# central.net
KiCad netlist of a schematic drawn in EAGLE
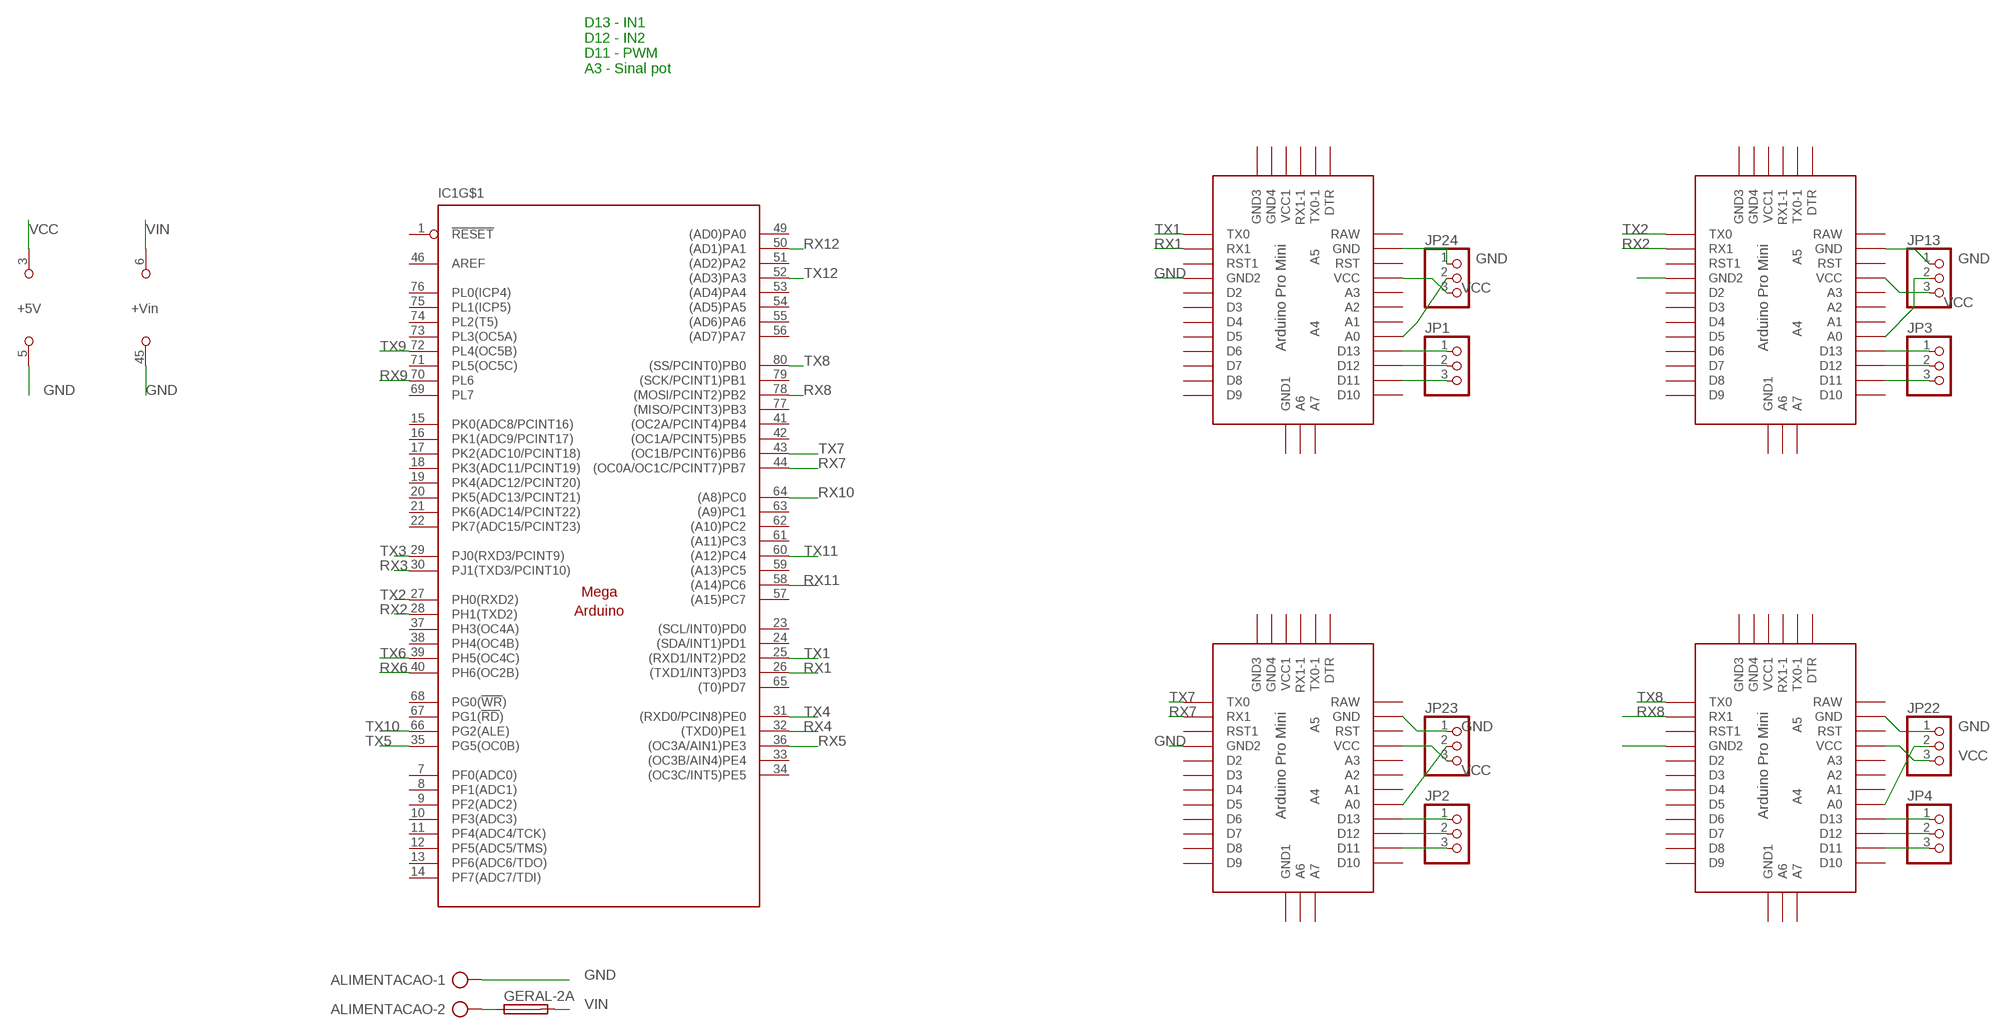
[diagram p0: schematic, sheet 1, part 1 of 2]
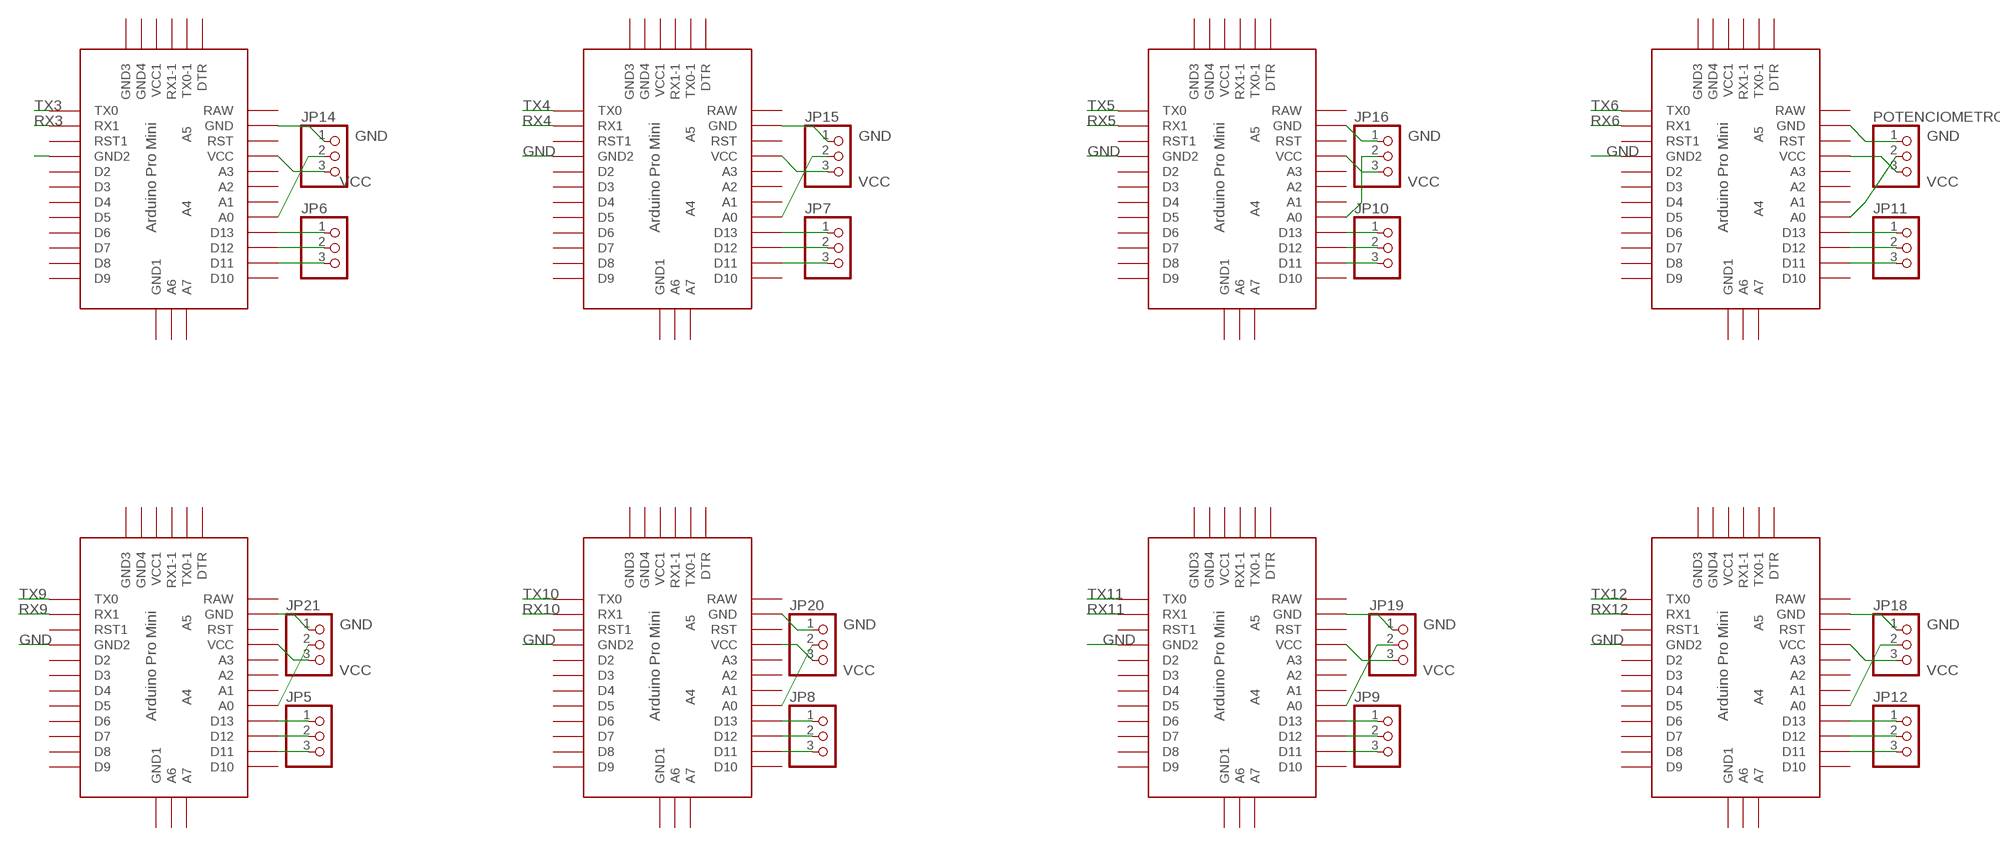
[diagram p1: schematic, sheet 1, part 2 of 2]

(export (version "E")
  (design (tool "Eeschema 10.0.6"))
  (components
    (comp (ref "ALIMENTACAO")
      (value "AK500/2")
      (footprint "eagle-import:AK500_2")
      (libsource (lib "eagle-import") (part "AK500/2"))
    )
    (comp (ref "GERAL-2A")
      (value "SH22,5A")
      (footprint "eagle-import:SH22,5A")
      (fields (field (name "MPN") "0031.7701.11"))
      (libsource (lib "eagle-import") (part "SH22,5A"))
    )
    (comp (ref "IC1")
      (value "MEGAARDUINO_22")
      (footprint "eagle-import:MEGA_ARDUINO_2")
      (libsource (lib "eagle-import") (part "MEGAARDUINO_22"))
    )
    (comp (ref "JP1")
      (value "PINHD-1X3")
      (footprint "eagle-import:1X03")
      (libsource (lib "eagle-import") (part "PINHD-1X3"))
    )
    (comp (ref "JP2")
      (value "PINHD-1X3")
      (footprint "eagle-import:1X03")
      (libsource (lib "eagle-import") (part "PINHD-1X3"))
    )
    (comp (ref "JP3")
      (value "PINHD-1X3")
      (footprint "eagle-import:1X03")
      (libsource (lib "eagle-import") (part "PINHD-1X3"))
    )
    (comp (ref "JP4")
      (value "PINHD-1X3")
      (footprint "eagle-import:1X03")
      (libsource (lib "eagle-import") (part "PINHD-1X3"))
    )
    (comp (ref "JP5")
      (value "PINHD-1X3")
      (footprint "eagle-import:1X03")
      (libsource (lib "eagle-import") (part "PINHD-1X3"))
    )
    (comp (ref "JP6")
      (value "PINHD-1X3")
      (footprint "eagle-import:1X03")
      (libsource (lib "eagle-import") (part "PINHD-1X3"))
    )
    (comp (ref "JP7")
      (value "PINHD-1X3")
      (footprint "eagle-import:1X03")
      (libsource (lib "eagle-import") (part "PINHD-1X3"))
    )
    (comp (ref "JP8")
      (value "PINHD-1X3")
      (footprint "eagle-import:1X03")
      (libsource (lib "eagle-import") (part "PINHD-1X3"))
    )
    (comp (ref "JP9")
      (value "PINHD-1X3")
      (footprint "eagle-import:1X03")
      (libsource (lib "eagle-import") (part "PINHD-1X3"))
    )
    (comp (ref "JP10")
      (value "PINHD-1X3")
      (footprint "eagle-import:1X03")
      (libsource (lib "eagle-import") (part "PINHD-1X3"))
    )
    (comp (ref "JP11")
      (value "PINHD-1X3")
      (footprint "eagle-import:1X03")
      (libsource (lib "eagle-import") (part "PINHD-1X3"))
    )
    (comp (ref "JP12")
      (value "PINHD-1X3")
      (footprint "eagle-import:1X03")
      (libsource (lib "eagle-import") (part "PINHD-1X3"))
    )
    (comp (ref "JP13")
      (value "PINHD-1X3")
      (footprint "eagle-import:1X03")
      (libsource (lib "eagle-import") (part "PINHD-1X3"))
    )
    (comp (ref "JP14")
      (value "PINHD-1X3")
      (footprint "eagle-import:1X03")
      (libsource (lib "eagle-import") (part "PINHD-1X3"))
    )
    (comp (ref "JP15")
      (value "PINHD-1X3")
      (footprint "eagle-import:1X03")
      (libsource (lib "eagle-import") (part "PINHD-1X3"))
    )
    (comp (ref "JP16")
      (value "PINHD-1X3")
      (footprint "eagle-import:1X03")
      (libsource (lib "eagle-import") (part "PINHD-1X3"))
    )
    (comp (ref "JP18")
      (value "PINHD-1X3")
      (footprint "eagle-import:1X03")
      (libsource (lib "eagle-import") (part "PINHD-1X3"))
    )
    (comp (ref "JP19")
      (value "PINHD-1X3")
      (footprint "eagle-import:1X03")
      (libsource (lib "eagle-import") (part "PINHD-1X3"))
    )
    (comp (ref "JP20")
      (value "PINHD-1X3")
      (footprint "eagle-import:1X03")
      (libsource (lib "eagle-import") (part "PINHD-1X3"))
    )
    (comp (ref "JP21")
      (value "PINHD-1X3")
      (footprint "eagle-import:1X03")
      (libsource (lib "eagle-import") (part "PINHD-1X3"))
    )
    (comp (ref "JP22")
      (value "PINHD-1X3")
      (footprint "eagle-import:1X03")
      (libsource (lib "eagle-import") (part "PINHD-1X3"))
    )
    (comp (ref "JP23")
      (value "PINHD-1X3")
      (footprint "eagle-import:1X03")
      (libsource (lib "eagle-import") (part "PINHD-1X3"))
    )
    (comp (ref "JP24")
      (value "PINHD-1X3")
      (footprint "eagle-import:1X03")
      (libsource (lib "eagle-import") (part "PINHD-1X3"))
    )
    (comp (ref "POTENCIOMETRO")
      (value "PINHD-1X3")
      (footprint "eagle-import:1X03")
      (libsource (lib "eagle-import") (part "PINHD-1X3"))
    )
    (comp (ref "U$1")
      (value "ABK-PRO-MINI")
      (footprint "eagle-import:ABK-PRO-MINI")
      (libsource (lib "eagle-import") (part "ABK-PRO-MINI"))
    )
    (comp (ref "U$2")
      (value "ABK-PRO-MINI")
      (footprint "eagle-import:ABK-PRO-MINI")
      (libsource (lib "eagle-import") (part "ABK-PRO-MINI"))
    )
    (comp (ref "U$3")
      (value "ABK-PRO-MINI")
      (footprint "eagle-import:ABK-PRO-MINI")
      (libsource (lib "eagle-import") (part "ABK-PRO-MINI"))
    )
    (comp (ref "U$4")
      (value "ABK-PRO-MINI")
      (footprint "eagle-import:ABK-PRO-MINI")
      (libsource (lib "eagle-import") (part "ABK-PRO-MINI"))
    )
    (comp (ref "U$5")
      (value "ABK-PRO-MINI")
      (footprint "eagle-import:ABK-PRO-MINI")
      (libsource (lib "eagle-import") (part "ABK-PRO-MINI"))
    )
    (comp (ref "U$6")
      (value "ABK-PRO-MINI")
      (footprint "eagle-import:ABK-PRO-MINI")
      (libsource (lib "eagle-import") (part "ABK-PRO-MINI"))
    )
    (comp (ref "U$7")
      (value "ABK-PRO-MINI")
      (footprint "eagle-import:ABK-PRO-MINI")
      (libsource (lib "eagle-import") (part "ABK-PRO-MINI"))
    )
    (comp (ref "U$8")
      (value "ABK-PRO-MINI")
      (footprint "eagle-import:ABK-PRO-MINI")
      (libsource (lib "eagle-import") (part "ABK-PRO-MINI"))
    )
    (comp (ref "U$9")
      (value "ABK-PRO-MINI")
      (footprint "eagle-import:ABK-PRO-MINI")
      (libsource (lib "eagle-import") (part "ABK-PRO-MINI"))
    )
    (comp (ref "U$10")
      (value "ABK-PRO-MINI")
      (footprint "eagle-import:ABK-PRO-MINI")
      (libsource (lib "eagle-import") (part "ABK-PRO-MINI"))
    )
    (comp (ref "U$11")
      (value "ABK-PRO-MINI")
      (footprint "eagle-import:ABK-PRO-MINI")
      (libsource (lib "eagle-import") (part "ABK-PRO-MINI"))
    )
    (comp (ref "U$12")
      (value "ABK-PRO-MINI")
      (footprint "eagle-import:ABK-PRO-MINI")
      (libsource (lib "eagle-import") (part "ABK-PRO-MINI"))
    )
  )
  (nets
    (net (code "1") (name "/GND") (class "Default")
      (node (ref "ALIMENTACAO") (pin "1") (pinfunction "KL_1") (pintype "passive"))
      (node (ref "IC1") (pin "45") (pinfunction "GND_45") (pintype "power_in"))
      (node (ref "IC1") (pin "5") (pinfunction "GND_5") (pintype "power_in"))
      (node (ref "JP13") (pin "1") (pinfunction "1_1") (pintype "passive"))
      (node (ref "JP14") (pin "1") (pinfunction "1_1") (pintype "passive"))
      (node (ref "JP15") (pin "1") (pinfunction "1_1") (pintype "passive"))
      (node (ref "JP16") (pin "1") (pinfunction "1_1") (pintype "passive"))
      (node (ref "JP18") (pin "1") (pinfunction "1_1") (pintype "passive"))
      (node (ref "JP19") (pin "1") (pinfunction "1_1") (pintype "passive"))
      (node (ref "JP20") (pin "1") (pinfunction "1_1") (pintype "passive"))
      (node (ref "JP21") (pin "1") (pinfunction "1_1") (pintype "passive"))
      (node (ref "JP22") (pin "1") (pinfunction "1_1") (pintype "passive"))
      (node (ref "JP23") (pin "1") (pinfunction "1_1") (pintype "passive"))
      (node (ref "JP24") (pin "1") (pinfunction "1_1") (pintype "passive"))
      (node (ref "POTENCIOMETRO") (pin "1") (pinfunction "1_1") (pintype "passive"))
      (node (ref "U$1") (pin "GND") (pinfunction "GND_GND") (pintype "bidirectional"))
      (node (ref "U$1") (pin "GND1") (pinfunction "GND2_GND1") (pintype "bidirectional"))
      (node (ref "U$10") (pin "GND") (pinfunction "GND_GND") (pintype "bidirectional"))
      (node (ref "U$10") (pin "GND1") (pinfunction "GND2_GND1") (pintype "bidirectional"))
      (node (ref "U$11") (pin "GND") (pinfunction "GND_GND") (pintype "bidirectional"))
      (node (ref "U$11") (pin "GND1") (pinfunction "GND2_GND1") (pintype "bidirectional"))
      (node (ref "U$12") (pin "GND") (pinfunction "GND_GND") (pintype "bidirectional"))
      (node (ref "U$12") (pin "GND1") (pinfunction "GND2_GND1") (pintype "bidirectional"))
      (node (ref "U$2") (pin "GND") (pinfunction "GND_GND") (pintype "bidirectional"))
      (node (ref "U$2") (pin "GND1") (pinfunction "GND2_GND1") (pintype "bidirectional"))
      (node (ref "U$3") (pin "GND") (pinfunction "GND_GND") (pintype "bidirectional"))
      (node (ref "U$3") (pin "GND1") (pinfunction "GND2_GND1") (pintype "bidirectional"))
      (node (ref "U$4") (pin "GND") (pinfunction "GND_GND") (pintype "bidirectional"))
      (node (ref "U$4") (pin "GND1") (pinfunction "GND2_GND1") (pintype "bidirectional"))
      (node (ref "U$5") (pin "GND") (pinfunction "GND_GND") (pintype "bidirectional"))
      (node (ref "U$5") (pin "GND1") (pinfunction "GND2_GND1") (pintype "bidirectional"))
      (node (ref "U$6") (pin "GND") (pinfunction "GND_GND") (pintype "bidirectional"))
      (node (ref "U$6") (pin "GND1") (pinfunction "GND2_GND1") (pintype "bidirectional"))
      (node (ref "U$7") (pin "GND") (pinfunction "GND_GND") (pintype "bidirectional"))
      (node (ref "U$7") (pin "GND1") (pinfunction "GND2_GND1") (pintype "bidirectional"))
      (node (ref "U$8") (pin "GND") (pinfunction "GND_GND") (pintype "bidirectional"))
      (node (ref "U$8") (pin "GND1") (pinfunction "GND2_GND1") (pintype "bidirectional"))
      (node (ref "U$9") (pin "GND") (pinfunction "GND_GND") (pintype "bidirectional"))
      (node (ref "U$9") (pin "GND1") (pinfunction "GND2_GND1") (pintype "bidirectional"))
    )
    (net (code "2") (name "/RX1") (class "Default")
      (node (ref "IC1") (pin "26") (pinfunction "(TXD1/INT3)PD3_26") (pintype "bidirectional"))
      (node (ref "U$1") (pin "RX1") (pinfunction "RX1_RX1") (pintype "bidirectional"))
    )
    (net (code "3") (name "/RX2") (class "Default")
      (node (ref "IC1") (pin "28") (pinfunction "PH1(TXD2)_28") (pintype "bidirectional"))
      (node (ref "U$7") (pin "RX1") (pinfunction "RX1_RX1") (pintype "bidirectional"))
    )
    (net (code "4") (name "/RX3") (class "Default")
      (node (ref "IC1") (pin "30") (pinfunction "PJ1(TXD3/PCINT10)_30") (pintype "bidirectional"))
      (node (ref "U$3") (pin "RX1") (pinfunction "RX1_RX1") (pintype "bidirectional"))
    )
    (net (code "5") (name "/RX4") (class "Default")
      (node (ref "IC1") (pin "32") (pinfunction "(TXD0)PE1_32") (pintype "bidirectional"))
      (node (ref "U$5") (pin "RX1") (pinfunction "RX1_RX1") (pintype "bidirectional"))
    )
    (net (code "6") (name "/RX5") (class "Default")
      (node (ref "IC1") (pin "36") (pinfunction "(OC3A/AIN1)PE3_36") (pintype "bidirectional"))
      (node (ref "U$9") (pin "RX1") (pinfunction "RX1_RX1") (pintype "bidirectional"))
    )
    (net (code "7") (name "/RX6") (class "Default")
      (node (ref "IC1") (pin "40") (pinfunction "PH6(OC2B)_40") (pintype "bidirectional"))
      (node (ref "U$11") (pin "RX1") (pinfunction "RX1_RX1") (pintype "bidirectional"))
    )
    (net (code "8") (name "/RX7") (class "Default")
      (node (ref "IC1") (pin "44") (pinfunction "(OC0A/OC1C/PCINT7)PB7_44") (pintype "bidirectional"))
      (node (ref "U$2") (pin "RX1") (pinfunction "RX1_RX1") (pintype "bidirectional"))
    )
    (net (code "9") (name "/RX8") (class "Default")
      (node (ref "IC1") (pin "78") (pinfunction "(MOSI/PCINT2)PB2_78") (pintype "bidirectional"))
      (node (ref "U$8") (pin "RX1") (pinfunction "RX1_RX1") (pintype "bidirectional"))
    )
    (net (code "10") (name "/RX9") (class "Default")
      (node (ref "IC1") (pin "70") (pinfunction "PL6_70") (pintype "bidirectional"))
      (node (ref "U$4") (pin "RX1") (pinfunction "RX1_RX1") (pintype "bidirectional"))
    )
    (net (code "11") (name "/RX10") (class "Default")
      (node (ref "IC1") (pin "64") (pinfunction "(A8)PC0_64") (pintype "bidirectional"))
      (node (ref "U$6") (pin "RX1") (pinfunction "RX1_RX1") (pintype "bidirectional"))
    )
    (net (code "12") (name "/RX11") (class "Default")
      (node (ref "IC1") (pin "58") (pinfunction "(A14)PC6_58") (pintype "bidirectional"))
      (node (ref "U$10") (pin "RX1") (pinfunction "RX1_RX1") (pintype "bidirectional"))
    )
    (net (code "13") (name "/RX12") (class "Default")
      (node (ref "IC1") (pin "50") (pinfunction "(AD1)PA1_50") (pintype "bidirectional"))
      (node (ref "U$12") (pin "RX1") (pinfunction "RX1_RX1") (pintype "bidirectional"))
    )
    (net (code "14") (name "/TX1") (class "Default")
      (node (ref "IC1") (pin "25") (pinfunction "(RXD1/INT2)PD2_25") (pintype "bidirectional"))
      (node (ref "U$1") (pin "TX0") (pinfunction "TX0_TX0") (pintype "bidirectional"))
    )
    (net (code "15") (name "/TX2") (class "Default")
      (node (ref "IC1") (pin "27") (pinfunction "PH0(RXD2)_27") (pintype "bidirectional"))
      (node (ref "U$7") (pin "TX0") (pinfunction "TX0_TX0") (pintype "bidirectional"))
    )
    (net (code "16") (name "/TX3") (class "Default")
      (node (ref "IC1") (pin "29") (pinfunction "PJ0(RXD3/PCINT9)_29") (pintype "bidirectional"))
      (node (ref "U$3") (pin "TX0") (pinfunction "TX0_TX0") (pintype "bidirectional"))
    )
    (net (code "17") (name "/TX4") (class "Default")
      (node (ref "IC1") (pin "31") (pinfunction "(RXD0/PCIN8)PE0_31") (pintype "bidirectional"))
      (node (ref "U$5") (pin "TX0") (pinfunction "TX0_TX0") (pintype "bidirectional"))
    )
    (net (code "18") (name "/TX5") (class "Default")
      (node (ref "IC1") (pin "35") (pinfunction "PG5(OC0B)_35") (pintype "bidirectional"))
      (node (ref "U$9") (pin "TX0") (pinfunction "TX0_TX0") (pintype "bidirectional"))
    )
    (net (code "19") (name "/TX6") (class "Default")
      (node (ref "IC1") (pin "39") (pinfunction "PH5(OC4C)_39") (pintype "bidirectional"))
      (node (ref "U$11") (pin "TX0") (pinfunction "TX0_TX0") (pintype "bidirectional"))
    )
    (net (code "20") (name "/TX7") (class "Default")
      (node (ref "IC1") (pin "43") (pinfunction "(OC1B/PCINT6)PB6_43") (pintype "bidirectional"))
      (node (ref "U$2") (pin "TX0") (pinfunction "TX0_TX0") (pintype "bidirectional"))
    )
    (net (code "21") (name "/TX8") (class "Default")
      (node (ref "IC1") (pin "80") (pinfunction "(SS/PCINT0)PB0_80") (pintype "bidirectional"))
      (node (ref "U$8") (pin "TX0") (pinfunction "TX0_TX0") (pintype "bidirectional"))
    )
    (net (code "22") (name "/TX9") (class "Default")
      (node (ref "IC1") (pin "72") (pinfunction "PL4(OC5B)_72") (pintype "bidirectional"))
      (node (ref "U$4") (pin "TX0") (pinfunction "TX0_TX0") (pintype "bidirectional"))
    )
    (net (code "23") (name "/TX10") (class "Default")
      (node (ref "IC1") (pin "66") (pinfunction "PG2(ALE)_66") (pintype "bidirectional"))
      (node (ref "U$6") (pin "TX0") (pinfunction "TX0_TX0") (pintype "bidirectional"))
    )
    (net (code "24") (name "/TX11") (class "Default")
      (node (ref "IC1") (pin "60") (pinfunction "(A12)PC4_60") (pintype "bidirectional"))
      (node (ref "U$10") (pin "TX0") (pinfunction "TX0_TX0") (pintype "bidirectional"))
    )
    (net (code "25") (name "/TX12") (class "Default")
      (node (ref "IC1") (pin "52") (pinfunction "(AD3)PA3_52") (pintype "bidirectional"))
      (node (ref "U$12") (pin "TX0") (pinfunction "TX0_TX0") (pintype "bidirectional"))
    )
    (net (code "26") (name "/VCC") (class "Default")
      (node (ref "IC1") (pin "3") (pinfunction "+5V_3") (pintype "power_in"))
      (node (ref "JP13") (pin "3") (pinfunction "3_3") (pintype "passive"))
      (node (ref "JP14") (pin "3") (pinfunction "3_3") (pintype "passive"))
      (node (ref "JP15") (pin "3") (pinfunction "3_3") (pintype "passive"))
      (node (ref "JP16") (pin "3") (pinfunction "3_3") (pintype "passive"))
      (node (ref "JP18") (pin "3") (pinfunction "3_3") (pintype "passive"))
      (node (ref "JP19") (pin "3") (pinfunction "3_3") (pintype "passive"))
      (node (ref "JP20") (pin "3") (pinfunction "3_3") (pintype "passive"))
      (node (ref "JP21") (pin "3") (pinfunction "3_3") (pintype "passive"))
      (node (ref "JP22") (pin "3") (pinfunction "3_3") (pintype "passive"))
      (node (ref "JP23") (pin "3") (pinfunction "3_3") (pintype "passive"))
      (node (ref "JP24") (pin "3") (pinfunction "3_3") (pintype "passive"))
      (node (ref "POTENCIOMETRO") (pin "3") (pinfunction "3_3") (pintype "passive"))
      (node (ref "U$1") (pin "VCC") (pinfunction "VCC_VCC") (pintype "bidirectional"))
      (node (ref "U$10") (pin "VCC") (pinfunction "VCC_VCC") (pintype "bidirectional"))
      (node (ref "U$11") (pin "VCC") (pinfunction "VCC_VCC") (pintype "bidirectional"))
      (node (ref "U$12") (pin "VCC") (pinfunction "VCC_VCC") (pintype "bidirectional"))
      (node (ref "U$2") (pin "VCC") (pinfunction "VCC_VCC") (pintype "bidirectional"))
      (node (ref "U$3") (pin "VCC") (pinfunction "VCC_VCC") (pintype "bidirectional"))
      (node (ref "U$4") (pin "VCC") (pinfunction "VCC_VCC") (pintype "bidirectional"))
      (node (ref "U$5") (pin "VCC") (pinfunction "VCC_VCC") (pintype "bidirectional"))
      (node (ref "U$6") (pin "VCC") (pinfunction "VCC_VCC") (pintype "bidirectional"))
      (node (ref "U$7") (pin "VCC") (pinfunction "VCC_VCC") (pintype "bidirectional"))
      (node (ref "U$8") (pin "VCC") (pinfunction "VCC_VCC") (pintype "bidirectional"))
      (node (ref "U$9") (pin "VCC") (pinfunction "VCC_VCC") (pintype "bidirectional"))
    )
    (net (code "27") (name "/VIN") (class "Default")
      (node (ref "GERAL-2A") (pin "2") (pinfunction "2_2") (pintype "passive"))
      (node (ref "IC1") (pin "6") (pinfunction "+VIN_6") (pintype "power_in"))
    )
    (net (code "28") (name "Net-(ALIMENTACAOB-KL)") (class "Default")
      (node (ref "ALIMENTACAO") (pin "2") (pinfunction "KL_2") (pintype "passive"))
      (node (ref "GERAL-2A") (pin "1") (pinfunction "1_1") (pintype "passive"))
    )
    (net (code "29") (name "Net-(JP1-Pad1)") (class "Default")
      (node (ref "JP1") (pin "1") (pinfunction "1_1") (pintype "passive"))
      (node (ref "U$1") (pin "D13") (pinfunction "D13_D13") (pintype "bidirectional"))
    )
    (net (code "30") (name "Net-(JP1-Pad2)") (class "Default")
      (node (ref "JP1") (pin "2") (pinfunction "2_2") (pintype "passive"))
      (node (ref "U$1") (pin "D12") (pinfunction "D12_D12") (pintype "bidirectional"))
    )
    (net (code "31") (name "Net-(JP1-Pad3)") (class "Default")
      (node (ref "JP1") (pin "3") (pinfunction "3_3") (pintype "passive"))
      (node (ref "U$1") (pin "D11") (pinfunction "D11_D11") (pintype "bidirectional"))
    )
    (net (code "32") (name "Net-(JP2-Pad1)") (class "Default")
      (node (ref "JP2") (pin "1") (pinfunction "1_1") (pintype "passive"))
      (node (ref "U$2") (pin "D13") (pinfunction "D13_D13") (pintype "bidirectional"))
    )
    (net (code "33") (name "Net-(JP2-Pad2)") (class "Default")
      (node (ref "JP2") (pin "2") (pinfunction "2_2") (pintype "passive"))
      (node (ref "U$2") (pin "D12") (pinfunction "D12_D12") (pintype "bidirectional"))
    )
    (net (code "34") (name "Net-(JP2-Pad3)") (class "Default")
      (node (ref "JP2") (pin "3") (pinfunction "3_3") (pintype "passive"))
      (node (ref "U$2") (pin "D11") (pinfunction "D11_D11") (pintype "bidirectional"))
    )
    (net (code "35") (name "Net-(JP3-Pad1)") (class "Default")
      (node (ref "JP3") (pin "1") (pinfunction "1_1") (pintype "passive"))
      (node (ref "U$7") (pin "D13") (pinfunction "D13_D13") (pintype "bidirectional"))
    )
    (net (code "36") (name "Net-(JP3-Pad2)") (class "Default")
      (node (ref "JP3") (pin "2") (pinfunction "2_2") (pintype "passive"))
      (node (ref "U$7") (pin "D12") (pinfunction "D12_D12") (pintype "bidirectional"))
    )
    (net (code "37") (name "Net-(JP3-Pad3)") (class "Default")
      (node (ref "JP3") (pin "3") (pinfunction "3_3") (pintype "passive"))
      (node (ref "U$7") (pin "D11") (pinfunction "D11_D11") (pintype "bidirectional"))
    )
    (net (code "38") (name "Net-(JP4-Pad1)") (class "Default")
      (node (ref "JP4") (pin "1") (pinfunction "1_1") (pintype "passive"))
      (node (ref "U$8") (pin "D13") (pinfunction "D13_D13") (pintype "bidirectional"))
    )
    (net (code "39") (name "Net-(JP4-Pad2)") (class "Default")
      (node (ref "JP4") (pin "2") (pinfunction "2_2") (pintype "passive"))
      (node (ref "U$8") (pin "D12") (pinfunction "D12_D12") (pintype "bidirectional"))
    )
    (net (code "40") (name "Net-(JP4-Pad3)") (class "Default")
      (node (ref "JP4") (pin "3") (pinfunction "3_3") (pintype "passive"))
      (node (ref "U$8") (pin "D11") (pinfunction "D11_D11") (pintype "bidirectional"))
    )
    (net (code "41") (name "Net-(JP5-Pad1)") (class "Default")
      (node (ref "JP5") (pin "1") (pinfunction "1_1") (pintype "passive"))
      (node (ref "U$4") (pin "D13") (pinfunction "D13_D13") (pintype "bidirectional"))
    )
    (net (code "42") (name "Net-(JP5-Pad2)") (class "Default")
      (node (ref "JP5") (pin "2") (pinfunction "2_2") (pintype "passive"))
      (node (ref "U$4") (pin "D12") (pinfunction "D12_D12") (pintype "bidirectional"))
    )
    (net (code "43") (name "Net-(JP5-Pad3)") (class "Default")
      (node (ref "JP5") (pin "3") (pinfunction "3_3") (pintype "passive"))
      (node (ref "U$4") (pin "D11") (pinfunction "D11_D11") (pintype "bidirectional"))
    )
    (net (code "44") (name "Net-(JP6-Pad1)") (class "Default")
      (node (ref "JP6") (pin "1") (pinfunction "1_1") (pintype "passive"))
      (node (ref "U$3") (pin "D13") (pinfunction "D13_D13") (pintype "bidirectional"))
    )
    (net (code "45") (name "Net-(JP6-Pad2)") (class "Default")
      (node (ref "JP6") (pin "2") (pinfunction "2_2") (pintype "passive"))
      (node (ref "U$3") (pin "D12") (pinfunction "D12_D12") (pintype "bidirectional"))
    )
    (net (code "46") (name "Net-(JP6-Pad3)") (class "Default")
      (node (ref "JP6") (pin "3") (pinfunction "3_3") (pintype "passive"))
      (node (ref "U$3") (pin "D11") (pinfunction "D11_D11") (pintype "bidirectional"))
    )
    (net (code "47") (name "Net-(JP7-Pad1)") (class "Default")
      (node (ref "JP7") (pin "1") (pinfunction "1_1") (pintype "passive"))
      (node (ref "U$5") (pin "D13") (pinfunction "D13_D13") (pintype "bidirectional"))
    )
    (net (code "48") (name "Net-(JP7-Pad2)") (class "Default")
      (node (ref "JP7") (pin "2") (pinfunction "2_2") (pintype "passive"))
      (node (ref "U$5") (pin "D12") (pinfunction "D12_D12") (pintype "bidirectional"))
    )
    (net (code "49") (name "Net-(JP7-Pad3)") (class "Default")
      (node (ref "JP7") (pin "3") (pinfunction "3_3") (pintype "passive"))
      (node (ref "U$5") (pin "D11") (pinfunction "D11_D11") (pintype "bidirectional"))
    )
    (net (code "50") (name "Net-(JP8-Pad1)") (class "Default")
      (node (ref "JP8") (pin "1") (pinfunction "1_1") (pintype "passive"))
      (node (ref "U$6") (pin "D13") (pinfunction "D13_D13") (pintype "bidirectional"))
    )
    (net (code "51") (name "Net-(JP8-Pad2)") (class "Default")
      (node (ref "JP8") (pin "2") (pinfunction "2_2") (pintype "passive"))
      (node (ref "U$6") (pin "D12") (pinfunction "D12_D12") (pintype "bidirectional"))
    )
    (net (code "52") (name "Net-(JP8-Pad3)") (class "Default")
      (node (ref "JP8") (pin "3") (pinfunction "3_3") (pintype "passive"))
      (node (ref "U$6") (pin "D11") (pinfunction "D11_D11") (pintype "bidirectional"))
    )
    (net (code "53") (name "Net-(JP9-Pad1)") (class "Default")
      (node (ref "JP9") (pin "1") (pinfunction "1_1") (pintype "passive"))
      (node (ref "U$10") (pin "D13") (pinfunction "D13_D13") (pintype "bidirectional"))
    )
    (net (code "54") (name "Net-(JP9-Pad2)") (class "Default")
      (node (ref "JP9") (pin "2") (pinfunction "2_2") (pintype "passive"))
      (node (ref "U$10") (pin "D12") (pinfunction "D12_D12") (pintype "bidirectional"))
    )
    (net (code "55") (name "Net-(JP9-Pad3)") (class "Default")
      (node (ref "JP9") (pin "3") (pinfunction "3_3") (pintype "passive"))
      (node (ref "U$10") (pin "D11") (pinfunction "D11_D11") (pintype "bidirectional"))
    )
    (net (code "56") (name "Net-(JP10-Pad1)") (class "Default")
      (node (ref "JP10") (pin "1") (pinfunction "1_1") (pintype "passive"))
      (node (ref "U$9") (pin "D13") (pinfunction "D13_D13") (pintype "bidirectional"))
    )
    (net (code "57") (name "Net-(JP10-Pad2)") (class "Default")
      (node (ref "JP10") (pin "2") (pinfunction "2_2") (pintype "passive"))
      (node (ref "U$9") (pin "D12") (pinfunction "D12_D12") (pintype "bidirectional"))
    )
    (net (code "58") (name "Net-(JP10-Pad3)") (class "Default")
      (node (ref "JP10") (pin "3") (pinfunction "3_3") (pintype "passive"))
      (node (ref "U$9") (pin "D11") (pinfunction "D11_D11") (pintype "bidirectional"))
    )
    (net (code "59") (name "Net-(JP11-Pad1)") (class "Default")
      (node (ref "JP11") (pin "1") (pinfunction "1_1") (pintype "passive"))
      (node (ref "U$11") (pin "D13") (pinfunction "D13_D13") (pintype "bidirectional"))
    )
    (net (code "60") (name "Net-(JP11-Pad2)") (class "Default")
      (node (ref "JP11") (pin "2") (pinfunction "2_2") (pintype "passive"))
      (node (ref "U$11") (pin "D12") (pinfunction "D12_D12") (pintype "bidirectional"))
    )
    (net (code "61") (name "Net-(JP11-Pad3)") (class "Default")
      (node (ref "JP11") (pin "3") (pinfunction "3_3") (pintype "passive"))
      (node (ref "U$11") (pin "D11") (pinfunction "D11_D11") (pintype "bidirectional"))
    )
    (net (code "62") (name "Net-(JP12-Pad1)") (class "Default")
      (node (ref "JP12") (pin "1") (pinfunction "1_1") (pintype "passive"))
      (node (ref "U$12") (pin "D13") (pinfunction "D13_D13") (pintype "bidirectional"))
    )
    (net (code "63") (name "Net-(JP12-Pad2)") (class "Default")
      (node (ref "JP12") (pin "2") (pinfunction "2_2") (pintype "passive"))
      (node (ref "U$12") (pin "D12") (pinfunction "D12_D12") (pintype "bidirectional"))
    )
    (net (code "64") (name "Net-(JP12-Pad3)") (class "Default")
      (node (ref "JP12") (pin "3") (pinfunction "3_3") (pintype "passive"))
      (node (ref "U$12") (pin "D11") (pinfunction "D11_D11") (pintype "bidirectional"))
    )
    (net (code "65") (name "Net-(JP13-Pad2)") (class "Default")
      (node (ref "JP13") (pin "2") (pinfunction "2_2") (pintype "passive"))
      (node (ref "U$7") (pin "A0") (pinfunction "A0_A0") (pintype "bidirectional"))
    )
    (net (code "66") (name "Net-(JP14-Pad2)") (class "Default")
      (node (ref "JP14") (pin "2") (pinfunction "2_2") (pintype "passive"))
      (node (ref "U$3") (pin "A0") (pinfunction "A0_A0") (pintype "bidirectional"))
    )
    (net (code "67") (name "Net-(JP15-Pad2)") (class "Default")
      (node (ref "JP15") (pin "2") (pinfunction "2_2") (pintype "passive"))
      (node (ref "U$5") (pin "A0") (pinfunction "A0_A0") (pintype "bidirectional"))
    )
    (net (code "68") (name "Net-(JP16-Pad2)") (class "Default")
      (node (ref "JP16") (pin "2") (pinfunction "2_2") (pintype "passive"))
      (node (ref "U$9") (pin "A0") (pinfunction "A0_A0") (pintype "bidirectional"))
    )
    (net (code "69") (name "Net-(JP18-Pad2)") (class "Default")
      (node (ref "JP18") (pin "2") (pinfunction "2_2") (pintype "passive"))
      (node (ref "U$12") (pin "A0") (pinfunction "A0_A0") (pintype "bidirectional"))
    )
    (net (code "70") (name "Net-(JP19-Pad2)") (class "Default")
      (node (ref "JP19") (pin "2") (pinfunction "2_2") (pintype "passive"))
      (node (ref "U$10") (pin "A0") (pinfunction "A0_A0") (pintype "bidirectional"))
    )
    (net (code "71") (name "Net-(JP20-Pad2)") (class "Default")
      (node (ref "JP20") (pin "2") (pinfunction "2_2") (pintype "passive"))
      (node (ref "U$6") (pin "A0") (pinfunction "A0_A0") (pintype "bidirectional"))
    )
    (net (code "72") (name "Net-(JP21-Pad2)") (class "Default")
      (node (ref "JP21") (pin "2") (pinfunction "2_2") (pintype "passive"))
      (node (ref "U$4") (pin "A0") (pinfunction "A0_A0") (pintype "bidirectional"))
    )
    (net (code "73") (name "Net-(JP22-Pad2)") (class "Default")
      (node (ref "JP22") (pin "2") (pinfunction "2_2") (pintype "passive"))
      (node (ref "U$8") (pin "A0") (pinfunction "A0_A0") (pintype "bidirectional"))
    )
    (net (code "74") (name "Net-(JP23-Pad2)") (class "Default")
      (node (ref "JP23") (pin "2") (pinfunction "2_2") (pintype "passive"))
      (node (ref "U$2") (pin "A0") (pinfunction "A0_A0") (pintype "bidirectional"))
    )
    (net (code "75") (name "Net-(JP24-Pad2)") (class "Default")
      (node (ref "JP24") (pin "2") (pinfunction "2_2") (pintype "passive"))
      (node (ref "U$1") (pin "A0") (pinfunction "A0_A0") (pintype "bidirectional"))
    )
    (net (code "76") (name "Net-(POTENCIOMETRO-Pad2)") (class "Default")
      (node (ref "POTENCIOMETRO") (pin "2") (pinfunction "2_2") (pintype "passive"))
      (node (ref "U$11") (pin "A0") (pinfunction "A0_A0") (pintype "bidirectional"))
    )
    (net (code "77") (name "unconnected-(IC1A-(A9)PC1-Pad63)") (class "Default")
      (node (ref "IC1") (pin "63") (pinfunction "(A9)PC1_63") (pintype "bidirectional"))
    )
    (net (code "78") (name "unconnected-(IC1A-(A10)PC2-Pad62)") (class "Default")
      (node (ref "IC1") (pin "62") (pinfunction "(A10)PC2_62") (pintype "bidirectional"))
    )
    (net (code "79") (name "unconnected-(IC1A-(A11)PC3-Pad61)") (class "Default")
      (node (ref "IC1") (pin "61") (pinfunction "(A11)PC3_61") (pintype "bidirectional"))
    )
    (net (code "80") (name "unconnected-(IC1A-(A13)PC5-Pad59)") (class "Default")
      (node (ref "IC1") (pin "59") (pinfunction "(A13)PC5_59") (pintype "bidirectional"))
    )
    (net (code "81") (name "unconnected-(IC1A-(A15)PC7-Pad57)") (class "Default")
      (node (ref "IC1") (pin "57") (pinfunction "(A15)PC7_57") (pintype "bidirectional"))
    )
    (net (code "82") (name "unconnected-(IC1A-(AD0)PA0-Pad49)") (class "Default")
      (node (ref "IC1") (pin "49") (pinfunction "(AD0)PA0_49") (pintype "bidirectional"))
    )
    (net (code "83") (name "unconnected-(IC1A-(AD2)PA2-Pad51)") (class "Default")
      (node (ref "IC1") (pin "51") (pinfunction "(AD2)PA2_51") (pintype "bidirectional"))
    )
    (net (code "84") (name "unconnected-(IC1A-(AD4)PA4-Pad53)") (class "Default")
      (node (ref "IC1") (pin "53") (pinfunction "(AD4)PA4_53") (pintype "bidirectional"))
    )
    (net (code "85") (name "unconnected-(IC1A-(AD5)PA5-Pad54)") (class "Default")
      (node (ref "IC1") (pin "54") (pinfunction "(AD5)PA5_54") (pintype "bidirectional"))
    )
    (net (code "86") (name "unconnected-(IC1A-(AD6)PA6-Pad55)") (class "Default")
      (node (ref "IC1") (pin "55") (pinfunction "(AD6)PA6_55") (pintype "bidirectional"))
    )
    (net (code "87") (name "unconnected-(IC1A-(AD7)PA7-Pad56)") (class "Default")
      (node (ref "IC1") (pin "56") (pinfunction "(AD7)PA7_56") (pintype "bidirectional"))
    )
    (net (code "88") (name "unconnected-(IC1A-(MISO{slash}PCINT3)PB3-Pad77)") (class "Default")
      (node (ref "IC1") (pin "77") (pinfunction "(MISO/PCINT3)PB3_77") (pintype "bidirectional"))
    )
    (net (code "89") (name "unconnected-(IC1A-(OC1A{slash}PCINT5)PB5-Pad42)") (class "Default")
      (node (ref "IC1") (pin "42") (pinfunction "(OC1A/PCINT5)PB5_42") (pintype "bidirectional"))
    )
    (net (code "90") (name "unconnected-(IC1A-(OC2A{slash}PCINT4)PB4-Pad41)") (class "Default")
      (node (ref "IC1") (pin "41") (pinfunction "(OC2A/PCINT4)PB4_41") (pintype "bidirectional"))
    )
    (net (code "91") (name "unconnected-(IC1A-(OC3B{slash}AIN4)PE4-Pad33)") (class "Default")
      (node (ref "IC1") (pin "33") (pinfunction "(OC3B/AIN4)PE4_33") (pintype "bidirectional"))
    )
    (net (code "92") (name "unconnected-(IC1A-(OC3C{slash}INT5)PE5-Pad34)") (class "Default")
      (node (ref "IC1") (pin "34") (pinfunction "(OC3C/INT5)PE5_34") (pintype "bidirectional"))
    )
    (net (code "93") (name "unconnected-(IC1A-(SCK{slash}PCINT1)PB1-Pad79)") (class "Default")
      (node (ref "IC1") (pin "79") (pinfunction "(SCK/PCINT1)PB1_79") (pintype "bidirectional"))
    )
    (net (code "94") (name "unconnected-(IC1A-(SCL{slash}INT0)PD0-Pad23)") (class "Default")
      (node (ref "IC1") (pin "23") (pinfunction "(SCL/INT0)PD0_23") (pintype "bidirectional"))
    )
    (net (code "95") (name "unconnected-(IC1A-(SDA{slash}INT1)PD1-Pad24)") (class "Default")
      (node (ref "IC1") (pin "24") (pinfunction "(SDA/INT1)PD1_24") (pintype "bidirectional"))
    )
    (net (code "96") (name "unconnected-(IC1A-(T0)PD7-Pad65)") (class "Default")
      (node (ref "IC1") (pin "65") (pinfunction "(T0)PD7_65") (pintype "bidirectional"))
    )
    (net (code "97") (name "unconnected-(IC1A-AREF-Pad46)") (class "Default")
      (node (ref "IC1") (pin "46") (pinfunction "AREF_46") (pintype "bidirectional"))
    )
    (net (code "98") (name "unconnected-(IC1A-PF0(ADC0)-Pad7)") (class "Default")
      (node (ref "IC1") (pin "7") (pinfunction "PF0(ADC0)_7") (pintype "bidirectional"))
    )
    (net (code "99") (name "unconnected-(IC1A-PF1(ADC1)-Pad8)") (class "Default")
      (node (ref "IC1") (pin "8") (pinfunction "PF1(ADC1)_8") (pintype "bidirectional"))
    )
    (net (code "100") (name "unconnected-(IC1A-PF2(ADC2)-Pad9)") (class "Default")
      (node (ref "IC1") (pin "9") (pinfunction "PF2(ADC2)_9") (pintype "bidirectional"))
    )
    (net (code "101") (name "unconnected-(IC1A-PF3(ADC3)-Pad10)") (class "Default")
      (node (ref "IC1") (pin "10") (pinfunction "PF3(ADC3)_10") (pintype "bidirectional"))
    )
    (net (code "102") (name "unconnected-(IC1A-PF4(ADC4{slash}TCK)-Pad11)") (class "Default")
      (node (ref "IC1") (pin "11") (pinfunction "PF4(ADC4/TCK)_11") (pintype "bidirectional"))
    )
    (net (code "103") (name "unconnected-(IC1A-PF5(ADC5{slash}TMS)-Pad12)") (class "Default")
      (node (ref "IC1") (pin "12") (pinfunction "PF5(ADC5/TMS)_12") (pintype "bidirectional"))
    )
    (net (code "104") (name "unconnected-(IC1A-PF6(ADC6{slash}TDO)-Pad13)") (class "Default")
      (node (ref "IC1") (pin "13") (pinfunction "PF6(ADC6/TDO)_13") (pintype "bidirectional"))
    )
    (net (code "105") (name "unconnected-(IC1A-PF7(ADC7{slash}TDI)-Pad14)") (class "Default")
      (node (ref "IC1") (pin "14") (pinfunction "PF7(ADC7/TDI)_14") (pintype "bidirectional"))
    )
    (net (code "106") (name "unconnected-(IC1A-PG0(~{WR})-Pad68)") (class "Default")
      (node (ref "IC1") (pin "68") (pinfunction "PG0(~{WR})_68") (pintype "bidirectional"))
    )
    (net (code "107") (name "unconnected-(IC1A-PG1(~{RD})-Pad67)") (class "Default")
      (node (ref "IC1") (pin "67") (pinfunction "PG1(~{RD})_67") (pintype "bidirectional"))
    )
    (net (code "108") (name "unconnected-(IC1A-PH3(OC4A)-Pad37)") (class "Default")
      (node (ref "IC1") (pin "37") (pinfunction "PH3(OC4A)_37") (pintype "bidirectional"))
    )
    (net (code "109") (name "unconnected-(IC1A-PH4(OC4B)-Pad38)") (class "Default")
      (node (ref "IC1") (pin "38") (pinfunction "PH4(OC4B)_38") (pintype "bidirectional"))
    )
    (net (code "110") (name "unconnected-(IC1A-PK0(ADC8{slash}PCINT16)-Pad15)") (class "Default")
      (node (ref "IC1") (pin "15") (pinfunction "PK0(ADC8/PCINT16)_15") (pintype "bidirectional"))
    )
    (net (code "111") (name "unconnected-(IC1A-PK1(ADC9{slash}PCINT17)-Pad16)") (class "Default")
      (node (ref "IC1") (pin "16") (pinfunction "PK1(ADC9/PCINT17)_16") (pintype "bidirectional"))
    )
    (net (code "112") (name "unconnected-(IC1A-PK2(ADC10{slash}PCINT18)-Pad17)") (class "Default")
      (node (ref "IC1") (pin "17") (pinfunction "PK2(ADC10/PCINT18)_17") (pintype "bidirectional"))
    )
    (net (code "113") (name "unconnected-(IC1A-PK3(ADC11{slash}PCINT19)-Pad18)") (class "Default")
      (node (ref "IC1") (pin "18") (pinfunction "PK3(ADC11/PCINT19)_18") (pintype "bidirectional"))
    )
    (net (code "114") (name "unconnected-(IC1A-PK4(ADC12{slash}PCINT20)-Pad19)") (class "Default")
      (node (ref "IC1") (pin "19") (pinfunction "PK4(ADC12/PCINT20)_19") (pintype "bidirectional"))
    )
    (net (code "115") (name "unconnected-(IC1A-PK5(ADC13{slash}PCINT21)-Pad20)") (class "Default")
      (node (ref "IC1") (pin "20") (pinfunction "PK5(ADC13/PCINT21)_20") (pintype "bidirectional"))
    )
    (net (code "116") (name "unconnected-(IC1A-PK6(ADC14{slash}PCINT22)-Pad21)") (class "Default")
      (node (ref "IC1") (pin "21") (pinfunction "PK6(ADC14/PCINT22)_21") (pintype "bidirectional"))
    )
    (net (code "117") (name "unconnected-(IC1A-PK7(ADC15{slash}PCINT23)-Pad22)") (class "Default")
      (node (ref "IC1") (pin "22") (pinfunction "PK7(ADC15/PCINT23)_22") (pintype "bidirectional"))
    )
    (net (code "118") (name "unconnected-(IC1A-PL0(ICP4)-Pad76)") (class "Default")
      (node (ref "IC1") (pin "76") (pinfunction "PL0(ICP4)_76") (pintype "bidirectional"))
    )
    (net (code "119") (name "unconnected-(IC1A-PL1(ICP5)-Pad75)") (class "Default")
      (node (ref "IC1") (pin "75") (pinfunction "PL1(ICP5)_75") (pintype "bidirectional"))
    )
    (net (code "120") (name "unconnected-(IC1A-PL2(T5)-Pad74)") (class "Default")
      (node (ref "IC1") (pin "74") (pinfunction "PL2(T5)_74") (pintype "bidirectional"))
    )
    (net (code "121") (name "unconnected-(IC1A-PL3(OC5A)-Pad73)") (class "Default")
      (node (ref "IC1") (pin "73") (pinfunction "PL3(OC5A)_73") (pintype "bidirectional"))
    )
    (net (code "122") (name "unconnected-(IC1A-PL5(OC5C)-Pad71)") (class "Default")
      (node (ref "IC1") (pin "71") (pinfunction "PL5(OC5C)_71") (pintype "bidirectional"))
    )
    (net (code "123") (name "unconnected-(IC1A-PL7-Pad69)") (class "Default")
      (node (ref "IC1") (pin "69") (pinfunction "PL7_69") (pintype "bidirectional"))
    )
    (net (code "124") (name "unconnected-(IC1A-~{RESET}-Pad1)") (class "Default")
      (node (ref "IC1") (pin "1") (pinfunction "~{RESET}_1") (pintype "bidirectional"))
    )
    (net (code "125") (name "unconnected-(U$1-GND1-PadGND4)") (class "Default")
      (node (ref "U$1") (pin "GND4") (pinfunction "GND1_GND4") (pintype "bidirectional"))
    )
    (net (code "126") (name "unconnected-(U$1-GND3-PadGND2)") (class "Default")
      (node (ref "U$1") (pin "GND2") (pinfunction "GND3_GND2") (pintype "bidirectional"))
    )
    (net (code "127") (name "unconnected-(U$1-GND4-PadGND3)") (class "Default")
      (node (ref "U$1") (pin "GND3") (pinfunction "GND4_GND3") (pintype "bidirectional"))
    )
    (net (code "128") (name "unconnected-(U$1-PadA1)") (class "Default")
      (node (ref "U$1") (pin "A1") (pinfunction "A1_A1") (pintype "bidirectional"))
    )
    (net (code "129") (name "unconnected-(U$1-PadA2)") (class "Default")
      (node (ref "U$1") (pin "A2") (pinfunction "A2_A2") (pintype "bidirectional"))
    )
    (net (code "130") (name "unconnected-(U$1-PadA3)") (class "Default")
      (node (ref "U$1") (pin "A3") (pinfunction "A3_A3") (pintype "bidirectional"))
    )
    (net (code "131") (name "unconnected-(U$1-PadA4)") (class "Default")
      (node (ref "U$1") (pin "A4") (pinfunction "A4_A4") (pintype "bidirectional"))
    )
    (net (code "132") (name "unconnected-(U$1-PadA5)") (class "Default")
      (node (ref "U$1") (pin "A5") (pinfunction "A5_A5") (pintype "bidirectional"))
    )
    (net (code "133") (name "unconnected-(U$1-PadA6)") (class "Default")
      (node (ref "U$1") (pin "A6") (pinfunction "A6_A6") (pintype "bidirectional"))
    )
    (net (code "134") (name "unconnected-(U$1-PadA7)") (class "Default")
      (node (ref "U$1") (pin "A7") (pinfunction "A7_A7") (pintype "bidirectional"))
    )
    (net (code "135") (name "unconnected-(U$1-PadD2)") (class "Default")
      (node (ref "U$1") (pin "D2") (pinfunction "D2_D2") (pintype "bidirectional"))
    )
    (net (code "136") (name "unconnected-(U$1-PadD3)") (class "Default")
      (node (ref "U$1") (pin "D3") (pinfunction "D3_D3") (pintype "bidirectional"))
    )
    (net (code "137") (name "unconnected-(U$1-PadD4)") (class "Default")
      (node (ref "U$1") (pin "D4") (pinfunction "D4_D4") (pintype "bidirectional"))
    )
    (net (code "138") (name "unconnected-(U$1-PadD5)") (class "Default")
      (node (ref "U$1") (pin "D5") (pinfunction "D5_D5") (pintype "bidirectional"))
    )
    (net (code "139") (name "unconnected-(U$1-PadD6)") (class "Default")
      (node (ref "U$1") (pin "D6") (pinfunction "D6_D6") (pintype "bidirectional"))
    )
    (net (code "140") (name "unconnected-(U$1-PadD7)") (class "Default")
      (node (ref "U$1") (pin "D7") (pinfunction "D7_D7") (pintype "bidirectional"))
    )
    (net (code "141") (name "unconnected-(U$1-PadD8)") (class "Default")
      (node (ref "U$1") (pin "D8") (pinfunction "D8_D8") (pintype "bidirectional"))
    )
    (net (code "142") (name "unconnected-(U$1-PadD9)") (class "Default")
      (node (ref "U$1") (pin "D9") (pinfunction "D9_D9") (pintype "bidirectional"))
    )
    (net (code "143") (name "unconnected-(U$1-PadD10)") (class "Default")
      (node (ref "U$1") (pin "D10") (pinfunction "D10_D10") (pintype "bidirectional"))
    )
    (net (code "144") (name "unconnected-(U$1-PadDTR)") (class "Default")
      (node (ref "U$1") (pin "DTR") (pinfunction "DTR_DTR") (pintype "bidirectional"))
    )
    (net (code "145") (name "unconnected-(U$1-PadRAW)") (class "Default")
      (node (ref "U$1") (pin "RAW") (pinfunction "RAW_RAW") (pintype "bidirectional"))
    )
    (net (code "146") (name "unconnected-(U$1-PadRST)") (class "Default")
      (node (ref "U$1") (pin "RST") (pinfunction "RST_RST") (pintype "bidirectional"))
    )
    (net (code "147") (name "unconnected-(U$1-PadRST1)") (class "Default")
      (node (ref "U$1") (pin "RST1") (pinfunction "RST1_RST1") (pintype "bidirectional"))
    )
    (net (code "148") (name "unconnected-(U$1-PadRX1-1)") (class "Default")
      (node (ref "U$1") (pin "RX1-1") (pinfunction "RX1-1_RX1-1") (pintype "bidirectional"))
    )
    (net (code "149") (name "unconnected-(U$1-PadTX0-1)") (class "Default")
      (node (ref "U$1") (pin "TX0-1") (pinfunction "TX0-1_TX0-1") (pintype "bidirectional"))
    )
    (net (code "150") (name "unconnected-(U$1-PadVCC1)") (class "Default")
      (node (ref "U$1") (pin "VCC1") (pinfunction "VCC1_VCC1") (pintype "bidirectional"))
    )
    (net (code "151") (name "unconnected-(U$2-GND1-PadGND4)") (class "Default")
      (node (ref "U$2") (pin "GND4") (pinfunction "GND1_GND4") (pintype "bidirectional"))
    )
    (net (code "152") (name "unconnected-(U$2-GND3-PadGND2)") (class "Default")
      (node (ref "U$2") (pin "GND2") (pinfunction "GND3_GND2") (pintype "bidirectional"))
    )
    (net (code "153") (name "unconnected-(U$2-GND4-PadGND3)") (class "Default")
      (node (ref "U$2") (pin "GND3") (pinfunction "GND4_GND3") (pintype "bidirectional"))
    )
    (net (code "154") (name "unconnected-(U$2-PadA1)") (class "Default")
      (node (ref "U$2") (pin "A1") (pinfunction "A1_A1") (pintype "bidirectional"))
    )
    (net (code "155") (name "unconnected-(U$2-PadA2)") (class "Default")
      (node (ref "U$2") (pin "A2") (pinfunction "A2_A2") (pintype "bidirectional"))
    )
    (net (code "156") (name "unconnected-(U$2-PadA3)") (class "Default")
      (node (ref "U$2") (pin "A3") (pinfunction "A3_A3") (pintype "bidirectional"))
    )
    (net (code "157") (name "unconnected-(U$2-PadA4)") (class "Default")
      (node (ref "U$2") (pin "A4") (pinfunction "A4_A4") (pintype "bidirectional"))
    )
    (net (code "158") (name "unconnected-(U$2-PadA5)") (class "Default")
      (node (ref "U$2") (pin "A5") (pinfunction "A5_A5") (pintype "bidirectional"))
    )
    (net (code "159") (name "unconnected-(U$2-PadA6)") (class "Default")
      (node (ref "U$2") (pin "A6") (pinfunction "A6_A6") (pintype "bidirectional"))
    )
    (net (code "160") (name "unconnected-(U$2-PadA7)") (class "Default")
      (node (ref "U$2") (pin "A7") (pinfunction "A7_A7") (pintype "bidirectional"))
    )
    (net (code "161") (name "unconnected-(U$2-PadD2)") (class "Default")
      (node (ref "U$2") (pin "D2") (pinfunction "D2_D2") (pintype "bidirectional"))
    )
    (net (code "162") (name "unconnected-(U$2-PadD3)") (class "Default")
      (node (ref "U$2") (pin "D3") (pinfunction "D3_D3") (pintype "bidirectional"))
    )
    (net (code "163") (name "unconnected-(U$2-PadD4)") (class "Default")
      (node (ref "U$2") (pin "D4") (pinfunction "D4_D4") (pintype "bidirectional"))
    )
    (net (code "164") (name "unconnected-(U$2-PadD5)") (class "Default")
      (node (ref "U$2") (pin "D5") (pinfunction "D5_D5") (pintype "bidirectional"))
    )
    (net (code "165") (name "unconnected-(U$2-PadD6)") (class "Default")
      (node (ref "U$2") (pin "D6") (pinfunction "D6_D6") (pintype "bidirectional"))
    )
    (net (code "166") (name "unconnected-(U$2-PadD7)") (class "Default")
      (node (ref "U$2") (pin "D7") (pinfunction "D7_D7") (pintype "bidirectional"))
    )
    (net (code "167") (name "unconnected-(U$2-PadD8)") (class "Default")
      (node (ref "U$2") (pin "D8") (pinfunction "D8_D8") (pintype "bidirectional"))
    )
    (net (code "168") (name "unconnected-(U$2-PadD9)") (class "Default")
      (node (ref "U$2") (pin "D9") (pinfunction "D9_D9") (pintype "bidirectional"))
    )
    (net (code "169") (name "unconnected-(U$2-PadD10)") (class "Default")
      (node (ref "U$2") (pin "D10") (pinfunction "D10_D10") (pintype "bidirectional"))
    )
    (net (code "170") (name "unconnected-(U$2-PadDTR)") (class "Default")
      (node (ref "U$2") (pin "DTR") (pinfunction "DTR_DTR") (pintype "bidirectional"))
    )
    (net (code "171") (name "unconnected-(U$2-PadRAW)") (class "Default")
      (node (ref "U$2") (pin "RAW") (pinfunction "RAW_RAW") (pintype "bidirectional"))
    )
    (net (code "172") (name "unconnected-(U$2-PadRST)") (class "Default")
      (node (ref "U$2") (pin "RST") (pinfunction "RST_RST") (pintype "bidirectional"))
    )
    (net (code "173") (name "unconnected-(U$2-PadRST1)") (class "Default")
      (node (ref "U$2") (pin "RST1") (pinfunction "RST1_RST1") (pintype "bidirectional"))
    )
    (net (code "174") (name "unconnected-(U$2-PadRX1-1)") (class "Default")
      (node (ref "U$2") (pin "RX1-1") (pinfunction "RX1-1_RX1-1") (pintype "bidirectional"))
    )
    (net (code "175") (name "unconnected-(U$2-PadTX0-1)") (class "Default")
      (node (ref "U$2") (pin "TX0-1") (pinfunction "TX0-1_TX0-1") (pintype "bidirectional"))
    )
    (net (code "176") (name "unconnected-(U$2-PadVCC1)") (class "Default")
      (node (ref "U$2") (pin "VCC1") (pinfunction "VCC1_VCC1") (pintype "bidirectional"))
    )
    (net (code "177") (name "unconnected-(U$3-GND1-PadGND4)") (class "Default")
      (node (ref "U$3") (pin "GND4") (pinfunction "GND1_GND4") (pintype "bidirectional"))
    )
    (net (code "178") (name "unconnected-(U$3-GND3-PadGND2)") (class "Default")
      (node (ref "U$3") (pin "GND2") (pinfunction "GND3_GND2") (pintype "bidirectional"))
    )
    (net (code "179") (name "unconnected-(U$3-GND4-PadGND3)") (class "Default")
      (node (ref "U$3") (pin "GND3") (pinfunction "GND4_GND3") (pintype "bidirectional"))
    )
    (net (code "180") (name "unconnected-(U$3-PadA1)") (class "Default")
      (node (ref "U$3") (pin "A1") (pinfunction "A1_A1") (pintype "bidirectional"))
    )
    (net (code "181") (name "unconnected-(U$3-PadA2)") (class "Default")
      (node (ref "U$3") (pin "A2") (pinfunction "A2_A2") (pintype "bidirectional"))
    )
    (net (code "182") (name "unconnected-(U$3-PadA3)") (class "Default")
      (node (ref "U$3") (pin "A3") (pinfunction "A3_A3") (pintype "bidirectional"))
    )
    (net (code "183") (name "unconnected-(U$3-PadA4)") (class "Default")
      (node (ref "U$3") (pin "A4") (pinfunction "A4_A4") (pintype "bidirectional"))
    )
    (net (code "184") (name "unconnected-(U$3-PadA5)") (class "Default")
      (node (ref "U$3") (pin "A5") (pinfunction "A5_A5") (pintype "bidirectional"))
    )
    (net (code "185") (name "unconnected-(U$3-PadA6)") (class "Default")
      (node (ref "U$3") (pin "A6") (pinfunction "A6_A6") (pintype "bidirectional"))
    )
    (net (code "186") (name "unconnected-(U$3-PadA7)") (class "Default")
      (node (ref "U$3") (pin "A7") (pinfunction "A7_A7") (pintype "bidirectional"))
    )
    (net (code "187") (name "unconnected-(U$3-PadD2)") (class "Default")
      (node (ref "U$3") (pin "D2") (pinfunction "D2_D2") (pintype "bidirectional"))
    )
    (net (code "188") (name "unconnected-(U$3-PadD3)") (class "Default")
      (node (ref "U$3") (pin "D3") (pinfunction "D3_D3") (pintype "bidirectional"))
    )
    (net (code "189") (name "unconnected-(U$3-PadD4)") (class "Default")
      (node (ref "U$3") (pin "D4") (pinfunction "D4_D4") (pintype "bidirectional"))
    )
    (net (code "190") (name "unconnected-(U$3-PadD5)") (class "Default")
      (node (ref "U$3") (pin "D5") (pinfunction "D5_D5") (pintype "bidirectional"))
    )
    (net (code "191") (name "unconnected-(U$3-PadD6)") (class "Default")
      (node (ref "U$3") (pin "D6") (pinfunction "D6_D6") (pintype "bidirectional"))
    )
    (net (code "192") (name "unconnected-(U$3-PadD7)") (class "Default")
      (node (ref "U$3") (pin "D7") (pinfunction "D7_D7") (pintype "bidirectional"))
    )
    (net (code "193") (name "unconnected-(U$3-PadD8)") (class "Default")
      (node (ref "U$3") (pin "D8") (pinfunction "D8_D8") (pintype "bidirectional"))
    )
    (net (code "194") (name "unconnected-(U$3-PadD9)") (class "Default")
      (node (ref "U$3") (pin "D9") (pinfunction "D9_D9") (pintype "bidirectional"))
    )
    (net (code "195") (name "unconnected-(U$3-PadD10)") (class "Default")
      (node (ref "U$3") (pin "D10") (pinfunction "D10_D10") (pintype "bidirectional"))
    )
    (net (code "196") (name "unconnected-(U$3-PadDTR)") (class "Default")
      (node (ref "U$3") (pin "DTR") (pinfunction "DTR_DTR") (pintype "bidirectional"))
    )
    (net (code "197") (name "unconnected-(U$3-PadRAW)") (class "Default")
      (node (ref "U$3") (pin "RAW") (pinfunction "RAW_RAW") (pintype "bidirectional"))
    )
    (net (code "198") (name "unconnected-(U$3-PadRST)") (class "Default")
      (node (ref "U$3") (pin "RST") (pinfunction "RST_RST") (pintype "bidirectional"))
    )
    (net (code "199") (name "unconnected-(U$3-PadRST1)") (class "Default")
      (node (ref "U$3") (pin "RST1") (pinfunction "RST1_RST1") (pintype "bidirectional"))
    )
    (net (code "200") (name "unconnected-(U$3-PadRX1-1)") (class "Default")
      (node (ref "U$3") (pin "RX1-1") (pinfunction "RX1-1_RX1-1") (pintype "bidirectional"))
    )
    (net (code "201") (name "unconnected-(U$3-PadTX0-1)") (class "Default")
      (node (ref "U$3") (pin "TX0-1") (pinfunction "TX0-1_TX0-1") (pintype "bidirectional"))
    )
    (net (code "202") (name "unconnected-(U$3-PadVCC1)") (class "Default")
      (node (ref "U$3") (pin "VCC1") (pinfunction "VCC1_VCC1") (pintype "bidirectional"))
    )
    (net (code "203") (name "unconnected-(U$4-GND1-PadGND4)") (class "Default")
      (node (ref "U$4") (pin "GND4") (pinfunction "GND1_GND4") (pintype "bidirectional"))
    )
    (net (code "204") (name "unconnected-(U$4-GND3-PadGND2)") (class "Default")
      (node (ref "U$4") (pin "GND2") (pinfunction "GND3_GND2") (pintype "bidirectional"))
    )
    (net (code "205") (name "unconnected-(U$4-GND4-PadGND3)") (class "Default")
      (node (ref "U$4") (pin "GND3") (pinfunction "GND4_GND3") (pintype "bidirectional"))
    )
    (net (code "206") (name "unconnected-(U$4-PadA1)") (class "Default")
      (node (ref "U$4") (pin "A1") (pinfunction "A1_A1") (pintype "bidirectional"))
    )
    (net (code "207") (name "unconnected-(U$4-PadA2)") (class "Default")
      (node (ref "U$4") (pin "A2") (pinfunction "A2_A2") (pintype "bidirectional"))
    )
    (net (code "208") (name "unconnected-(U$4-PadA3)") (class "Default")
      (node (ref "U$4") (pin "A3") (pinfunction "A3_A3") (pintype "bidirectional"))
    )
    (net (code "209") (name "unconnected-(U$4-PadA4)") (class "Default")
      (node (ref "U$4") (pin "A4") (pinfunction "A4_A4") (pintype "bidirectional"))
    )
    (net (code "210") (name "unconnected-(U$4-PadA5)") (class "Default")
      (node (ref "U$4") (pin "A5") (pinfunction "A5_A5") (pintype "bidirectional"))
    )
    (net (code "211") (name "unconnected-(U$4-PadA6)") (class "Default")
      (node (ref "U$4") (pin "A6") (pinfunction "A6_A6") (pintype "bidirectional"))
    )
    (net (code "212") (name "unconnected-(U$4-PadA7)") (class "Default")
      (node (ref "U$4") (pin "A7") (pinfunction "A7_A7") (pintype "bidirectional"))
    )
    (net (code "213") (name "unconnected-(U$4-PadD2)") (class "Default")
      (node (ref "U$4") (pin "D2") (pinfunction "D2_D2") (pintype "bidirectional"))
    )
    (net (code "214") (name "unconnected-(U$4-PadD3)") (class "Default")
      (node (ref "U$4") (pin "D3") (pinfunction "D3_D3") (pintype "bidirectional"))
    )
    (net (code "215") (name "unconnected-(U$4-PadD4)") (class "Default")
      (node (ref "U$4") (pin "D4") (pinfunction "D4_D4") (pintype "bidirectional"))
    )
    (net (code "216") (name "unconnected-(U$4-PadD5)") (class "Default")
      (node (ref "U$4") (pin "D5") (pinfunction "D5_D5") (pintype "bidirectional"))
    )
    (net (code "217") (name "unconnected-(U$4-PadD6)") (class "Default")
      (node (ref "U$4") (pin "D6") (pinfunction "D6_D6") (pintype "bidirectional"))
    )
    (net (code "218") (name "unconnected-(U$4-PadD7)") (class "Default")
      (node (ref "U$4") (pin "D7") (pinfunction "D7_D7") (pintype "bidirectional"))
    )
    (net (code "219") (name "unconnected-(U$4-PadD8)") (class "Default")
      (node (ref "U$4") (pin "D8") (pinfunction "D8_D8") (pintype "bidirectional"))
    )
    (net (code "220") (name "unconnected-(U$4-PadD9)") (class "Default")
      (node (ref "U$4") (pin "D9") (pinfunction "D9_D9") (pintype "bidirectional"))
    )
    (net (code "221") (name "unconnected-(U$4-PadD10)") (class "Default")
      (node (ref "U$4") (pin "D10") (pinfunction "D10_D10") (pintype "bidirectional"))
    )
    (net (code "222") (name "unconnected-(U$4-PadDTR)") (class "Default")
      (node (ref "U$4") (pin "DTR") (pinfunction "DTR_DTR") (pintype "bidirectional"))
    )
    (net (code "223") (name "unconnected-(U$4-PadRAW)") (class "Default")
      (node (ref "U$4") (pin "RAW") (pinfunction "RAW_RAW") (pintype "bidirectional"))
    )
    (net (code "224") (name "unconnected-(U$4-PadRST)") (class "Default")
      (node (ref "U$4") (pin "RST") (pinfunction "RST_RST") (pintype "bidirectional"))
    )
    (net (code "225") (name "unconnected-(U$4-PadRST1)") (class "Default")
      (node (ref "U$4") (pin "RST1") (pinfunction "RST1_RST1") (pintype "bidirectional"))
    )
    (net (code "226") (name "unconnected-(U$4-PadRX1-1)") (class "Default")
      (node (ref "U$4") (pin "RX1-1") (pinfunction "RX1-1_RX1-1") (pintype "bidirectional"))
    )
    (net (code "227") (name "unconnected-(U$4-PadTX0-1)") (class "Default")
      (node (ref "U$4") (pin "TX0-1") (pinfunction "TX0-1_TX0-1") (pintype "bidirectional"))
    )
    (net (code "228") (name "unconnected-(U$4-PadVCC1)") (class "Default")
      (node (ref "U$4") (pin "VCC1") (pinfunction "VCC1_VCC1") (pintype "bidirectional"))
    )
    (net (code "229") (name "unconnected-(U$5-GND1-PadGND4)") (class "Default")
      (node (ref "U$5") (pin "GND4") (pinfunction "GND1_GND4") (pintype "bidirectional"))
    )
    (net (code "230") (name "unconnected-(U$5-GND3-PadGND2)") (class "Default")
      (node (ref "U$5") (pin "GND2") (pinfunction "GND3_GND2") (pintype "bidirectional"))
    )
    (net (code "231") (name "unconnected-(U$5-GND4-PadGND3)") (class "Default")
      (node (ref "U$5") (pin "GND3") (pinfunction "GND4_GND3") (pintype "bidirectional"))
    )
    (net (code "232") (name "unconnected-(U$5-PadA1)") (class "Default")
      (node (ref "U$5") (pin "A1") (pinfunction "A1_A1") (pintype "bidirectional"))
    )
    (net (code "233") (name "unconnected-(U$5-PadA2)") (class "Default")
      (node (ref "U$5") (pin "A2") (pinfunction "A2_A2") (pintype "bidirectional"))
    )
    (net (code "234") (name "unconnected-(U$5-PadA3)") (class "Default")
      (node (ref "U$5") (pin "A3") (pinfunction "A3_A3") (pintype "bidirectional"))
    )
    (net (code "235") (name "unconnected-(U$5-PadA4)") (class "Default")
      (node (ref "U$5") (pin "A4") (pinfunction "A4_A4") (pintype "bidirectional"))
    )
    (net (code "236") (name "unconnected-(U$5-PadA5)") (class "Default")
      (node (ref "U$5") (pin "A5") (pinfunction "A5_A5") (pintype "bidirectional"))
    )
    (net (code "237") (name "unconnected-(U$5-PadA6)") (class "Default")
      (node (ref "U$5") (pin "A6") (pinfunction "A6_A6") (pintype "bidirectional"))
    )
    (net (code "238") (name "unconnected-(U$5-PadA7)") (class "Default")
      (node (ref "U$5") (pin "A7") (pinfunction "A7_A7") (pintype "bidirectional"))
    )
    (net (code "239") (name "unconnected-(U$5-PadD2)") (class "Default")
      (node (ref "U$5") (pin "D2") (pinfunction "D2_D2") (pintype "bidirectional"))
    )
    (net (code "240") (name "unconnected-(U$5-PadD3)") (class "Default")
      (node (ref "U$5") (pin "D3") (pinfunction "D3_D3") (pintype "bidirectional"))
    )
    (net (code "241") (name "unconnected-(U$5-PadD4)") (class "Default")
      (node (ref "U$5") (pin "D4") (pinfunction "D4_D4") (pintype "bidirectional"))
    )
    (net (code "242") (name "unconnected-(U$5-PadD5)") (class "Default")
      (node (ref "U$5") (pin "D5") (pinfunction "D5_D5") (pintype "bidirectional"))
    )
    (net (code "243") (name "unconnected-(U$5-PadD6)") (class "Default")
      (node (ref "U$5") (pin "D6") (pinfunction "D6_D6") (pintype "bidirectional"))
    )
    (net (code "244") (name "unconnected-(U$5-PadD7)") (class "Default")
      (node (ref "U$5") (pin "D7") (pinfunction "D7_D7") (pintype "bidirectional"))
    )
    (net (code "245") (name "unconnected-(U$5-PadD8)") (class "Default")
      (node (ref "U$5") (pin "D8") (pinfunction "D8_D8") (pintype "bidirectional"))
    )
    (net (code "246") (name "unconnected-(U$5-PadD9)") (class "Default")
      (node (ref "U$5") (pin "D9") (pinfunction "D9_D9") (pintype "bidirectional"))
    )
    (net (code "247") (name "unconnected-(U$5-PadD10)") (class "Default")
      (node (ref "U$5") (pin "D10") (pinfunction "D10_D10") (pintype "bidirectional"))
    )
    (net (code "248") (name "unconnected-(U$5-PadDTR)") (class "Default")
      (node (ref "U$5") (pin "DTR") (pinfunction "DTR_DTR") (pintype "bidirectional"))
    )
    (net (code "249") (name "unconnected-(U$5-PadRAW)") (class "Default")
      (node (ref "U$5") (pin "RAW") (pinfunction "RAW_RAW") (pintype "bidirectional"))
    )
    (net (code "250") (name "unconnected-(U$5-PadRST)") (class "Default")
      (node (ref "U$5") (pin "RST") (pinfunction "RST_RST") (pintype "bidirectional"))
    )
    (net (code "251") (name "unconnected-(U$5-PadRST1)") (class "Default")
      (node (ref "U$5") (pin "RST1") (pinfunction "RST1_RST1") (pintype "bidirectional"))
    )
    (net (code "252") (name "unconnected-(U$5-PadRX1-1)") (class "Default")
      (node (ref "U$5") (pin "RX1-1") (pinfunction "RX1-1_RX1-1") (pintype "bidirectional"))
    )
    (net (code "253") (name "unconnected-(U$5-PadTX0-1)") (class "Default")
      (node (ref "U$5") (pin "TX0-1") (pinfunction "TX0-1_TX0-1") (pintype "bidirectional"))
    )
    (net (code "254") (name "unconnected-(U$5-PadVCC1)") (class "Default")
      (node (ref "U$5") (pin "VCC1") (pinfunction "VCC1_VCC1") (pintype "bidirectional"))
    )
    (net (code "255") (name "unconnected-(U$6-GND1-PadGND4)") (class "Default")
      (node (ref "U$6") (pin "GND4") (pinfunction "GND1_GND4") (pintype "bidirectional"))
    )
    (net (code "256") (name "unconnected-(U$6-GND3-PadGND2)") (class "Default")
      (node (ref "U$6") (pin "GND2") (pinfunction "GND3_GND2") (pintype "bidirectional"))
    )
    (net (code "257") (name "unconnected-(U$6-GND4-PadGND3)") (class "Default")
      (node (ref "U$6") (pin "GND3") (pinfunction "GND4_GND3") (pintype "bidirectional"))
    )
    (net (code "258") (name "unconnected-(U$6-PadA1)") (class "Default")
      (node (ref "U$6") (pin "A1") (pinfunction "A1_A1") (pintype "bidirectional"))
    )
    (net (code "259") (name "unconnected-(U$6-PadA2)") (class "Default")
      (node (ref "U$6") (pin "A2") (pinfunction "A2_A2") (pintype "bidirectional"))
    )
    (net (code "260") (name "unconnected-(U$6-PadA3)") (class "Default")
      (node (ref "U$6") (pin "A3") (pinfunction "A3_A3") (pintype "bidirectional"))
    )
    (net (code "261") (name "unconnected-(U$6-PadA4)") (class "Default")
      (node (ref "U$6") (pin "A4") (pinfunction "A4_A4") (pintype "bidirectional"))
    )
    (net (code "262") (name "unconnected-(U$6-PadA5)") (class "Default")
      (node (ref "U$6") (pin "A5") (pinfunction "A5_A5") (pintype "bidirectional"))
    )
    (net (code "263") (name "unconnected-(U$6-PadA6)") (class "Default")
      (node (ref "U$6") (pin "A6") (pinfunction "A6_A6") (pintype "bidirectional"))
    )
    (net (code "264") (name "unconnected-(U$6-PadA7)") (class "Default")
      (node (ref "U$6") (pin "A7") (pinfunction "A7_A7") (pintype "bidirectional"))
    )
    (net (code "265") (name "unconnected-(U$6-PadD2)") (class "Default")
      (node (ref "U$6") (pin "D2") (pinfunction "D2_D2") (pintype "bidirectional"))
    )
    (net (code "266") (name "unconnected-(U$6-PadD3)") (class "Default")
      (node (ref "U$6") (pin "D3") (pinfunction "D3_D3") (pintype "bidirectional"))
    )
    (net (code "267") (name "unconnected-(U$6-PadD4)") (class "Default")
      (node (ref "U$6") (pin "D4") (pinfunction "D4_D4") (pintype "bidirectional"))
    )
    (net (code "268") (name "unconnected-(U$6-PadD5)") (class "Default")
      (node (ref "U$6") (pin "D5") (pinfunction "D5_D5") (pintype "bidirectional"))
    )
    (net (code "269") (name "unconnected-(U$6-PadD6)") (class "Default")
      (node (ref "U$6") (pin "D6") (pinfunction "D6_D6") (pintype "bidirectional"))
    )
    (net (code "270") (name "unconnected-(U$6-PadD7)") (class "Default")
      (node (ref "U$6") (pin "D7") (pinfunction "D7_D7") (pintype "bidirectional"))
    )
    (net (code "271") (name "unconnected-(U$6-PadD8)") (class "Default")
      (node (ref "U$6") (pin "D8") (pinfunction "D8_D8") (pintype "bidirectional"))
    )
    (net (code "272") (name "unconnected-(U$6-PadD9)") (class "Default")
      (node (ref "U$6") (pin "D9") (pinfunction "D9_D9") (pintype "bidirectional"))
    )
    (net (code "273") (name "unconnected-(U$6-PadD10)") (class "Default")
      (node (ref "U$6") (pin "D10") (pinfunction "D10_D10") (pintype "bidirectional"))
    )
    (net (code "274") (name "unconnected-(U$6-PadDTR)") (class "Default")
      (node (ref "U$6") (pin "DTR") (pinfunction "DTR_DTR") (pintype "bidirectional"))
    )
    (net (code "275") (name "unconnected-(U$6-PadRAW)") (class "Default")
      (node (ref "U$6") (pin "RAW") (pinfunction "RAW_RAW") (pintype "bidirectional"))
    )
    (net (code "276") (name "unconnected-(U$6-PadRST)") (class "Default")
      (node (ref "U$6") (pin "RST") (pinfunction "RST_RST") (pintype "bidirectional"))
    )
    (net (code "277") (name "unconnected-(U$6-PadRST1)") (class "Default")
      (node (ref "U$6") (pin "RST1") (pinfunction "RST1_RST1") (pintype "bidirectional"))
    )
    (net (code "278") (name "unconnected-(U$6-PadRX1-1)") (class "Default")
      (node (ref "U$6") (pin "RX1-1") (pinfunction "RX1-1_RX1-1") (pintype "bidirectional"))
    )
    (net (code "279") (name "unconnected-(U$6-PadTX0-1)") (class "Default")
      (node (ref "U$6") (pin "TX0-1") (pinfunction "TX0-1_TX0-1") (pintype "bidirectional"))
    )
    (net (code "280") (name "unconnected-(U$6-PadVCC1)") (class "Default")
      (node (ref "U$6") (pin "VCC1") (pinfunction "VCC1_VCC1") (pintype "bidirectional"))
    )
    (net (code "281") (name "unconnected-(U$7-GND1-PadGND4)") (class "Default")
      (node (ref "U$7") (pin "GND4") (pinfunction "GND1_GND4") (pintype "bidirectional"))
    )
    (net (code "282") (name "unconnected-(U$7-GND3-PadGND2)") (class "Default")
      (node (ref "U$7") (pin "GND2") (pinfunction "GND3_GND2") (pintype "bidirectional"))
    )
    (net (code "283") (name "unconnected-(U$7-GND4-PadGND3)") (class "Default")
      (node (ref "U$7") (pin "GND3") (pinfunction "GND4_GND3") (pintype "bidirectional"))
    )
    (net (code "284") (name "unconnected-(U$7-PadA1)") (class "Default")
      (node (ref "U$7") (pin "A1") (pinfunction "A1_A1") (pintype "bidirectional"))
    )
    (net (code "285") (name "unconnected-(U$7-PadA2)") (class "Default")
      (node (ref "U$7") (pin "A2") (pinfunction "A2_A2") (pintype "bidirectional"))
    )
    (net (code "286") (name "unconnected-(U$7-PadA3)") (class "Default")
      (node (ref "U$7") (pin "A3") (pinfunction "A3_A3") (pintype "bidirectional"))
    )
    (net (code "287") (name "unconnected-(U$7-PadA4)") (class "Default")
      (node (ref "U$7") (pin "A4") (pinfunction "A4_A4") (pintype "bidirectional"))
    )
    (net (code "288") (name "unconnected-(U$7-PadA5)") (class "Default")
      (node (ref "U$7") (pin "A5") (pinfunction "A5_A5") (pintype "bidirectional"))
    )
    (net (code "289") (name "unconnected-(U$7-PadA6)") (class "Default")
      (node (ref "U$7") (pin "A6") (pinfunction "A6_A6") (pintype "bidirectional"))
    )
    (net (code "290") (name "unconnected-(U$7-PadA7)") (class "Default")
      (node (ref "U$7") (pin "A7") (pinfunction "A7_A7") (pintype "bidirectional"))
    )
    (net (code "291") (name "unconnected-(U$7-PadD2)") (class "Default")
      (node (ref "U$7") (pin "D2") (pinfunction "D2_D2") (pintype "bidirectional"))
    )
    (net (code "292") (name "unconnected-(U$7-PadD3)") (class "Default")
      (node (ref "U$7") (pin "D3") (pinfunction "D3_D3") (pintype "bidirectional"))
    )
    (net (code "293") (name "unconnected-(U$7-PadD4)") (class "Default")
      (node (ref "U$7") (pin "D4") (pinfunction "D4_D4") (pintype "bidirectional"))
    )
    (net (code "294") (name "unconnected-(U$7-PadD5)") (class "Default")
      (node (ref "U$7") (pin "D5") (pinfunction "D5_D5") (pintype "bidirectional"))
    )
    (net (code "295") (name "unconnected-(U$7-PadD6)") (class "Default")
      (node (ref "U$7") (pin "D6") (pinfunction "D6_D6") (pintype "bidirectional"))
    )
    (net (code "296") (name "unconnected-(U$7-PadD7)") (class "Default")
      (node (ref "U$7") (pin "D7") (pinfunction "D7_D7") (pintype "bidirectional"))
    )
    (net (code "297") (name "unconnected-(U$7-PadD8)") (class "Default")
      (node (ref "U$7") (pin "D8") (pinfunction "D8_D8") (pintype "bidirectional"))
    )
    (net (code "298") (name "unconnected-(U$7-PadD9)") (class "Default")
      (node (ref "U$7") (pin "D9") (pinfunction "D9_D9") (pintype "bidirectional"))
    )
    (net (code "299") (name "unconnected-(U$7-PadD10)") (class "Default")
      (node (ref "U$7") (pin "D10") (pinfunction "D10_D10") (pintype "bidirectional"))
    )
    (net (code "300") (name "unconnected-(U$7-PadDTR)") (class "Default")
      (node (ref "U$7") (pin "DTR") (pinfunction "DTR_DTR") (pintype "bidirectional"))
    )
    (net (code "301") (name "unconnected-(U$7-PadRAW)") (class "Default")
      (node (ref "U$7") (pin "RAW") (pinfunction "RAW_RAW") (pintype "bidirectional"))
    )
    (net (code "302") (name "unconnected-(U$7-PadRST)") (class "Default")
      (node (ref "U$7") (pin "RST") (pinfunction "RST_RST") (pintype "bidirectional"))
    )
    (net (code "303") (name "unconnected-(U$7-PadRST1)") (class "Default")
      (node (ref "U$7") (pin "RST1") (pinfunction "RST1_RST1") (pintype "bidirectional"))
    )
    (net (code "304") (name "unconnected-(U$7-PadRX1-1)") (class "Default")
      (node (ref "U$7") (pin "RX1-1") (pinfunction "RX1-1_RX1-1") (pintype "bidirectional"))
    )
    (net (code "305") (name "unconnected-(U$7-PadTX0-1)") (class "Default")
      (node (ref "U$7") (pin "TX0-1") (pinfunction "TX0-1_TX0-1") (pintype "bidirectional"))
    )
    (net (code "306") (name "unconnected-(U$7-PadVCC1)") (class "Default")
      (node (ref "U$7") (pin "VCC1") (pinfunction "VCC1_VCC1") (pintype "bidirectional"))
    )
    (net (code "307") (name "unconnected-(U$8-GND1-PadGND4)") (class "Default")
      (node (ref "U$8") (pin "GND4") (pinfunction "GND1_GND4") (pintype "bidirectional"))
    )
    (net (code "308") (name "unconnected-(U$8-GND3-PadGND2)") (class "Default")
      (node (ref "U$8") (pin "GND2") (pinfunction "GND3_GND2") (pintype "bidirectional"))
    )
    (net (code "309") (name "unconnected-(U$8-GND4-PadGND3)") (class "Default")
      (node (ref "U$8") (pin "GND3") (pinfunction "GND4_GND3") (pintype "bidirectional"))
    )
    (net (code "310") (name "unconnected-(U$8-PadA1)") (class "Default")
      (node (ref "U$8") (pin "A1") (pinfunction "A1_A1") (pintype "bidirectional"))
    )
    (net (code "311") (name "unconnected-(U$8-PadA2)") (class "Default")
      (node (ref "U$8") (pin "A2") (pinfunction "A2_A2") (pintype "bidirectional"))
    )
    (net (code "312") (name "unconnected-(U$8-PadA3)") (class "Default")
      (node (ref "U$8") (pin "A3") (pinfunction "A3_A3") (pintype "bidirectional"))
    )
    (net (code "313") (name "unconnected-(U$8-PadA4)") (class "Default")
      (node (ref "U$8") (pin "A4") (pinfunction "A4_A4") (pintype "bidirectional"))
    )
    (net (code "314") (name "unconnected-(U$8-PadA5)") (class "Default")
      (node (ref "U$8") (pin "A5") (pinfunction "A5_A5") (pintype "bidirectional"))
    )
    (net (code "315") (name "unconnected-(U$8-PadA6)") (class "Default")
      (node (ref "U$8") (pin "A6") (pinfunction "A6_A6") (pintype "bidirectional"))
    )
    (net (code "316") (name "unconnected-(U$8-PadA7)") (class "Default")
      (node (ref "U$8") (pin "A7") (pinfunction "A7_A7") (pintype "bidirectional"))
    )
    (net (code "317") (name "unconnected-(U$8-PadD2)") (class "Default")
      (node (ref "U$8") (pin "D2") (pinfunction "D2_D2") (pintype "bidirectional"))
    )
    (net (code "318") (name "unconnected-(U$8-PadD3)") (class "Default")
      (node (ref "U$8") (pin "D3") (pinfunction "D3_D3") (pintype "bidirectional"))
    )
    (net (code "319") (name "unconnected-(U$8-PadD4)") (class "Default")
      (node (ref "U$8") (pin "D4") (pinfunction "D4_D4") (pintype "bidirectional"))
    )
    (net (code "320") (name "unconnected-(U$8-PadD5)") (class "Default")
      (node (ref "U$8") (pin "D5") (pinfunction "D5_D5") (pintype "bidirectional"))
    )
    (net (code "321") (name "unconnected-(U$8-PadD6)") (class "Default")
      (node (ref "U$8") (pin "D6") (pinfunction "D6_D6") (pintype "bidirectional"))
    )
    (net (code "322") (name "unconnected-(U$8-PadD7)") (class "Default")
      (node (ref "U$8") (pin "D7") (pinfunction "D7_D7") (pintype "bidirectional"))
    )
    (net (code "323") (name "unconnected-(U$8-PadD8)") (class "Default")
      (node (ref "U$8") (pin "D8") (pinfunction "D8_D8") (pintype "bidirectional"))
    )
    (net (code "324") (name "unconnected-(U$8-PadD9)") (class "Default")
      (node (ref "U$8") (pin "D9") (pinfunction "D9_D9") (pintype "bidirectional"))
    )
    (net (code "325") (name "unconnected-(U$8-PadD10)") (class "Default")
      (node (ref "U$8") (pin "D10") (pinfunction "D10_D10") (pintype "bidirectional"))
    )
    (net (code "326") (name "unconnected-(U$8-PadDTR)") (class "Default")
      (node (ref "U$8") (pin "DTR") (pinfunction "DTR_DTR") (pintype "bidirectional"))
    )
    (net (code "327") (name "unconnected-(U$8-PadRAW)") (class "Default")
      (node (ref "U$8") (pin "RAW") (pinfunction "RAW_RAW") (pintype "bidirectional"))
    )
    (net (code "328") (name "unconnected-(U$8-PadRST)") (class "Default")
      (node (ref "U$8") (pin "RST") (pinfunction "RST_RST") (pintype "bidirectional"))
    )
    (net (code "329") (name "unconnected-(U$8-PadRST1)") (class "Default")
      (node (ref "U$8") (pin "RST1") (pinfunction "RST1_RST1") (pintype "bidirectional"))
    )
    (net (code "330") (name "unconnected-(U$8-PadRX1-1)") (class "Default")
      (node (ref "U$8") (pin "RX1-1") (pinfunction "RX1-1_RX1-1") (pintype "bidirectional"))
    )
    (net (code "331") (name "unconnected-(U$8-PadTX0-1)") (class "Default")
      (node (ref "U$8") (pin "TX0-1") (pinfunction "TX0-1_TX0-1") (pintype "bidirectional"))
    )
    (net (code "332") (name "unconnected-(U$8-PadVCC1)") (class "Default")
      (node (ref "U$8") (pin "VCC1") (pinfunction "VCC1_VCC1") (pintype "bidirectional"))
    )
    (net (code "333") (name "unconnected-(U$9-GND1-PadGND4)") (class "Default")
      (node (ref "U$9") (pin "GND4") (pinfunction "GND1_GND4") (pintype "bidirectional"))
    )
    (net (code "334") (name "unconnected-(U$9-GND3-PadGND2)") (class "Default")
      (node (ref "U$9") (pin "GND2") (pinfunction "GND3_GND2") (pintype "bidirectional"))
    )
    (net (code "335") (name "unconnected-(U$9-GND4-PadGND3)") (class "Default")
      (node (ref "U$9") (pin "GND3") (pinfunction "GND4_GND3") (pintype "bidirectional"))
    )
    (net (code "336") (name "unconnected-(U$9-PadA1)") (class "Default")
      (node (ref "U$9") (pin "A1") (pinfunction "A1_A1") (pintype "bidirectional"))
    )
    (net (code "337") (name "unconnected-(U$9-PadA2)") (class "Default")
      (node (ref "U$9") (pin "A2") (pinfunction "A2_A2") (pintype "bidirectional"))
    )
    (net (code "338") (name "unconnected-(U$9-PadA3)") (class "Default")
      (node (ref "U$9") (pin "A3") (pinfunction "A3_A3") (pintype "bidirectional"))
    )
    (net (code "339") (name "unconnected-(U$9-PadA4)") (class "Default")
      (node (ref "U$9") (pin "A4") (pinfunction "A4_A4") (pintype "bidirectional"))
    )
    (net (code "340") (name "unconnected-(U$9-PadA5)") (class "Default")
      (node (ref "U$9") (pin "A5") (pinfunction "A5_A5") (pintype "bidirectional"))
    )
    (net (code "341") (name "unconnected-(U$9-PadA6)") (class "Default")
      (node (ref "U$9") (pin "A6") (pinfunction "A6_A6") (pintype "bidirectional"))
    )
    (net (code "342") (name "unconnected-(U$9-PadA7)") (class "Default")
      (node (ref "U$9") (pin "A7") (pinfunction "A7_A7") (pintype "bidirectional"))
    )
    (net (code "343") (name "unconnected-(U$9-PadD2)") (class "Default")
      (node (ref "U$9") (pin "D2") (pinfunction "D2_D2") (pintype "bidirectional"))
    )
    (net (code "344") (name "unconnected-(U$9-PadD3)") (class "Default")
      (node (ref "U$9") (pin "D3") (pinfunction "D3_D3") (pintype "bidirectional"))
    )
    (net (code "345") (name "unconnected-(U$9-PadD4)") (class "Default")
      (node (ref "U$9") (pin "D4") (pinfunction "D4_D4") (pintype "bidirectional"))
    )
    (net (code "346") (name "unconnected-(U$9-PadD5)") (class "Default")
      (node (ref "U$9") (pin "D5") (pinfunction "D5_D5") (pintype "bidirectional"))
    )
    (net (code "347") (name "unconnected-(U$9-PadD6)") (class "Default")
      (node (ref "U$9") (pin "D6") (pinfunction "D6_D6") (pintype "bidirectional"))
    )
    (net (code "348") (name "unconnected-(U$9-PadD7)") (class "Default")
      (node (ref "U$9") (pin "D7") (pinfunction "D7_D7") (pintype "bidirectional"))
    )
    (net (code "349") (name "unconnected-(U$9-PadD8)") (class "Default")
      (node (ref "U$9") (pin "D8") (pinfunction "D8_D8") (pintype "bidirectional"))
    )
    (net (code "350") (name "unconnected-(U$9-PadD9)") (class "Default")
      (node (ref "U$9") (pin "D9") (pinfunction "D9_D9") (pintype "bidirectional"))
    )
    (net (code "351") (name "unconnected-(U$9-PadD10)") (class "Default")
      (node (ref "U$9") (pin "D10") (pinfunction "D10_D10") (pintype "bidirectional"))
    )
    (net (code "352") (name "unconnected-(U$9-PadDTR)") (class "Default")
      (node (ref "U$9") (pin "DTR") (pinfunction "DTR_DTR") (pintype "bidirectional"))
    )
    (net (code "353") (name "unconnected-(U$9-PadRAW)") (class "Default")
      (node (ref "U$9") (pin "RAW") (pinfunction "RAW_RAW") (pintype "bidirectional"))
    )
    (net (code "354") (name "unconnected-(U$9-PadRST)") (class "Default")
      (node (ref "U$9") (pin "RST") (pinfunction "RST_RST") (pintype "bidirectional"))
    )
    (net (code "355") (name "unconnected-(U$9-PadRST1)") (class "Default")
      (node (ref "U$9") (pin "RST1") (pinfunction "RST1_RST1") (pintype "bidirectional"))
    )
    (net (code "356") (name "unconnected-(U$9-PadRX1-1)") (class "Default")
      (node (ref "U$9") (pin "RX1-1") (pinfunction "RX1-1_RX1-1") (pintype "bidirectional"))
    )
    (net (code "357") (name "unconnected-(U$9-PadTX0-1)") (class "Default")
      (node (ref "U$9") (pin "TX0-1") (pinfunction "TX0-1_TX0-1") (pintype "bidirectional"))
    )
    (net (code "358") (name "unconnected-(U$9-PadVCC1)") (class "Default")
      (node (ref "U$9") (pin "VCC1") (pinfunction "VCC1_VCC1") (pintype "bidirectional"))
    )
    (net (code "359") (name "unconnected-(U$10-GND1-PadGND4)") (class "Default")
      (node (ref "U$10") (pin "GND4") (pinfunction "GND1_GND4") (pintype "bidirectional"))
    )
    (net (code "360") (name "unconnected-(U$10-GND3-PadGND2)") (class "Default")
      (node (ref "U$10") (pin "GND2") (pinfunction "GND3_GND2") (pintype "bidirectional"))
    )
    (net (code "361") (name "unconnected-(U$10-GND4-PadGND3)") (class "Default")
      (node (ref "U$10") (pin "GND3") (pinfunction "GND4_GND3") (pintype "bidirectional"))
    )
    (net (code "362") (name "unconnected-(U$10-PadA1)") (class "Default")
      (node (ref "U$10") (pin "A1") (pinfunction "A1_A1") (pintype "bidirectional"))
    )
    (net (code "363") (name "unconnected-(U$10-PadA2)") (class "Default")
      (node (ref "U$10") (pin "A2") (pinfunction "A2_A2") (pintype "bidirectional"))
    )
    (net (code "364") (name "unconnected-(U$10-PadA3)") (class "Default")
      (node (ref "U$10") (pin "A3") (pinfunction "A3_A3") (pintype "bidirectional"))
    )
    (net (code "365") (name "unconnected-(U$10-PadA4)") (class "Default")
      (node (ref "U$10") (pin "A4") (pinfunction "A4_A4") (pintype "bidirectional"))
    )
    (net (code "366") (name "unconnected-(U$10-PadA5)") (class "Default")
      (node (ref "U$10") (pin "A5") (pinfunction "A5_A5") (pintype "bidirectional"))
    )
    (net (code "367") (name "unconnected-(U$10-PadA6)") (class "Default")
      (node (ref "U$10") (pin "A6") (pinfunction "A6_A6") (pintype "bidirectional"))
    )
    (net (code "368") (name "unconnected-(U$10-PadA7)") (class "Default")
      (node (ref "U$10") (pin "A7") (pinfunction "A7_A7") (pintype "bidirectional"))
    )
    (net (code "369") (name "unconnected-(U$10-PadD2)") (class "Default")
      (node (ref "U$10") (pin "D2") (pinfunction "D2_D2") (pintype "bidirectional"))
    )
    (net (code "370") (name "unconnected-(U$10-PadD3)") (class "Default")
      (node (ref "U$10") (pin "D3") (pinfunction "D3_D3") (pintype "bidirectional"))
    )
    (net (code "371") (name "unconnected-(U$10-PadD4)") (class "Default")
      (node (ref "U$10") (pin "D4") (pinfunction "D4_D4") (pintype "bidirectional"))
    )
    (net (code "372") (name "unconnected-(U$10-PadD5)") (class "Default")
      (node (ref "U$10") (pin "D5") (pinfunction "D5_D5") (pintype "bidirectional"))
    )
    (net (code "373") (name "unconnected-(U$10-PadD6)") (class "Default")
      (node (ref "U$10") (pin "D6") (pinfunction "D6_D6") (pintype "bidirectional"))
    )
    (net (code "374") (name "unconnected-(U$10-PadD7)") (class "Default")
      (node (ref "U$10") (pin "D7") (pinfunction "D7_D7") (pintype "bidirectional"))
    )
    (net (code "375") (name "unconnected-(U$10-PadD8)") (class "Default")
      (node (ref "U$10") (pin "D8") (pinfunction "D8_D8") (pintype "bidirectional"))
    )
    (net (code "376") (name "unconnected-(U$10-PadD9)") (class "Default")
      (node (ref "U$10") (pin "D9") (pinfunction "D9_D9") (pintype "bidirectional"))
    )
    (net (code "377") (name "unconnected-(U$10-PadD10)") (class "Default")
      (node (ref "U$10") (pin "D10") (pinfunction "D10_D10") (pintype "bidirectional"))
    )
    (net (code "378") (name "unconnected-(U$10-PadDTR)") (class "Default")
      (node (ref "U$10") (pin "DTR") (pinfunction "DTR_DTR") (pintype "bidirectional"))
    )
    (net (code "379") (name "unconnected-(U$10-PadRAW)") (class "Default")
      (node (ref "U$10") (pin "RAW") (pinfunction "RAW_RAW") (pintype "bidirectional"))
    )
    (net (code "380") (name "unconnected-(U$10-PadRST)") (class "Default")
      (node (ref "U$10") (pin "RST") (pinfunction "RST_RST") (pintype "bidirectional"))
    )
    (net (code "381") (name "unconnected-(U$10-PadRST1)") (class "Default")
      (node (ref "U$10") (pin "RST1") (pinfunction "RST1_RST1") (pintype "bidirectional"))
    )
    (net (code "382") (name "unconnected-(U$10-PadRX1-1)") (class "Default")
      (node (ref "U$10") (pin "RX1-1") (pinfunction "RX1-1_RX1-1") (pintype "bidirectional"))
    )
    (net (code "383") (name "unconnected-(U$10-PadTX0-1)") (class "Default")
      (node (ref "U$10") (pin "TX0-1") (pinfunction "TX0-1_TX0-1") (pintype "bidirectional"))
    )
    (net (code "384") (name "unconnected-(U$10-PadVCC1)") (class "Default")
      (node (ref "U$10") (pin "VCC1") (pinfunction "VCC1_VCC1") (pintype "bidirectional"))
    )
    (net (code "385") (name "unconnected-(U$11-GND1-PadGND4)") (class "Default")
      (node (ref "U$11") (pin "GND4") (pinfunction "GND1_GND4") (pintype "bidirectional"))
    )
    (net (code "386") (name "unconnected-(U$11-GND3-PadGND2)") (class "Default")
      (node (ref "U$11") (pin "GND2") (pinfunction "GND3_GND2") (pintype "bidirectional"))
    )
    (net (code "387") (name "unconnected-(U$11-GND4-PadGND3)") (class "Default")
      (node (ref "U$11") (pin "GND3") (pinfunction "GND4_GND3") (pintype "bidirectional"))
    )
    (net (code "388") (name "unconnected-(U$11-PadA1)") (class "Default")
      (node (ref "U$11") (pin "A1") (pinfunction "A1_A1") (pintype "bidirectional"))
    )
    (net (code "389") (name "unconnected-(U$11-PadA2)") (class "Default")
      (node (ref "U$11") (pin "A2") (pinfunction "A2_A2") (pintype "bidirectional"))
    )
    (net (code "390") (name "unconnected-(U$11-PadA3)") (class "Default")
      (node (ref "U$11") (pin "A3") (pinfunction "A3_A3") (pintype "bidirectional"))
    )
    (net (code "391") (name "unconnected-(U$11-PadA4)") (class "Default")
      (node (ref "U$11") (pin "A4") (pinfunction "A4_A4") (pintype "bidirectional"))
    )
    (net (code "392") (name "unconnected-(U$11-PadA5)") (class "Default")
      (node (ref "U$11") (pin "A5") (pinfunction "A5_A5") (pintype "bidirectional"))
    )
    (net (code "393") (name "unconnected-(U$11-PadA6)") (class "Default")
      (node (ref "U$11") (pin "A6") (pinfunction "A6_A6") (pintype "bidirectional"))
    )
    (net (code "394") (name "unconnected-(U$11-PadA7)") (class "Default")
      (node (ref "U$11") (pin "A7") (pinfunction "A7_A7") (pintype "bidirectional"))
    )
    (net (code "395") (name "unconnected-(U$11-PadD2)") (class "Default")
      (node (ref "U$11") (pin "D2") (pinfunction "D2_D2") (pintype "bidirectional"))
    )
    (net (code "396") (name "unconnected-(U$11-PadD3)") (class "Default")
      (node (ref "U$11") (pin "D3") (pinfunction "D3_D3") (pintype "bidirectional"))
    )
    (net (code "397") (name "unconnected-(U$11-PadD4)") (class "Default")
      (node (ref "U$11") (pin "D4") (pinfunction "D4_D4") (pintype "bidirectional"))
    )
    (net (code "398") (name "unconnected-(U$11-PadD5)") (class "Default")
      (node (ref "U$11") (pin "D5") (pinfunction "D5_D5") (pintype "bidirectional"))
    )
    (net (code "399") (name "unconnected-(U$11-PadD6)") (class "Default")
      (node (ref "U$11") (pin "D6") (pinfunction "D6_D6") (pintype "bidirectional"))
    )
    (net (code "400") (name "unconnected-(U$11-PadD7)") (class "Default")
      (node (ref "U$11") (pin "D7") (pinfunction "D7_D7") (pintype "bidirectional"))
    )
    (net (code "401") (name "unconnected-(U$11-PadD8)") (class "Default")
      (node (ref "U$11") (pin "D8") (pinfunction "D8_D8") (pintype "bidirectional"))
    )
    (net (code "402") (name "unconnected-(U$11-PadD9)") (class "Default")
      (node (ref "U$11") (pin "D9") (pinfunction "D9_D9") (pintype "bidirectional"))
    )
    (net (code "403") (name "unconnected-(U$11-PadD10)") (class "Default")
      (node (ref "U$11") (pin "D10") (pinfunction "D10_D10") (pintype "bidirectional"))
    )
    (net (code "404") (name "unconnected-(U$11-PadDTR)") (class "Default")
      (node (ref "U$11") (pin "DTR") (pinfunction "DTR_DTR") (pintype "bidirectional"))
    )
    (net (code "405") (name "unconnected-(U$11-PadRAW)") (class "Default")
      (node (ref "U$11") (pin "RAW") (pinfunction "RAW_RAW") (pintype "bidirectional"))
    )
    (net (code "406") (name "unconnected-(U$11-PadRST)") (class "Default")
      (node (ref "U$11") (pin "RST") (pinfunction "RST_RST") (pintype "bidirectional"))
    )
    (net (code "407") (name "unconnected-(U$11-PadRST1)") (class "Default")
      (node (ref "U$11") (pin "RST1") (pinfunction "RST1_RST1") (pintype "bidirectional"))
    )
    (net (code "408") (name "unconnected-(U$11-PadRX1-1)") (class "Default")
      (node (ref "U$11") (pin "RX1-1") (pinfunction "RX1-1_RX1-1") (pintype "bidirectional"))
    )
    (net (code "409") (name "unconnected-(U$11-PadTX0-1)") (class "Default")
      (node (ref "U$11") (pin "TX0-1") (pinfunction "TX0-1_TX0-1") (pintype "bidirectional"))
    )
    (net (code "410") (name "unconnected-(U$11-PadVCC1)") (class "Default")
      (node (ref "U$11") (pin "VCC1") (pinfunction "VCC1_VCC1") (pintype "bidirectional"))
    )
    (net (code "411") (name "unconnected-(U$12-GND1-PadGND4)") (class "Default")
      (node (ref "U$12") (pin "GND4") (pinfunction "GND1_GND4") (pintype "bidirectional"))
    )
    (net (code "412") (name "unconnected-(U$12-GND3-PadGND2)") (class "Default")
      (node (ref "U$12") (pin "GND2") (pinfunction "GND3_GND2") (pintype "bidirectional"))
    )
    (net (code "413") (name "unconnected-(U$12-GND4-PadGND3)") (class "Default")
      (node (ref "U$12") (pin "GND3") (pinfunction "GND4_GND3") (pintype "bidirectional"))
    )
    (net (code "414") (name "unconnected-(U$12-PadA1)") (class "Default")
      (node (ref "U$12") (pin "A1") (pinfunction "A1_A1") (pintype "bidirectional"))
    )
    (net (code "415") (name "unconnected-(U$12-PadA2)") (class "Default")
      (node (ref "U$12") (pin "A2") (pinfunction "A2_A2") (pintype "bidirectional"))
    )
    (net (code "416") (name "unconnected-(U$12-PadA3)") (class "Default")
      (node (ref "U$12") (pin "A3") (pinfunction "A3_A3") (pintype "bidirectional"))
    )
    (net (code "417") (name "unconnected-(U$12-PadA4)") (class "Default")
      (node (ref "U$12") (pin "A4") (pinfunction "A4_A4") (pintype "bidirectional"))
    )
    (net (code "418") (name "unconnected-(U$12-PadA5)") (class "Default")
      (node (ref "U$12") (pin "A5") (pinfunction "A5_A5") (pintype "bidirectional"))
    )
    (net (code "419") (name "unconnected-(U$12-PadA6)") (class "Default")
      (node (ref "U$12") (pin "A6") (pinfunction "A6_A6") (pintype "bidirectional"))
    )
    (net (code "420") (name "unconnected-(U$12-PadA7)") (class "Default")
      (node (ref "U$12") (pin "A7") (pinfunction "A7_A7") (pintype "bidirectional"))
    )
    (net (code "421") (name "unconnected-(U$12-PadD2)") (class "Default")
      (node (ref "U$12") (pin "D2") (pinfunction "D2_D2") (pintype "bidirectional"))
    )
    (net (code "422") (name "unconnected-(U$12-PadD3)") (class "Default")
      (node (ref "U$12") (pin "D3") (pinfunction "D3_D3") (pintype "bidirectional"))
    )
    (net (code "423") (name "unconnected-(U$12-PadD4)") (class "Default")
      (node (ref "U$12") (pin "D4") (pinfunction "D4_D4") (pintype "bidirectional"))
    )
    (net (code "424") (name "unconnected-(U$12-PadD5)") (class "Default")
      (node (ref "U$12") (pin "D5") (pinfunction "D5_D5") (pintype "bidirectional"))
    )
    (net (code "425") (name "unconnected-(U$12-PadD6)") (class "Default")
      (node (ref "U$12") (pin "D6") (pinfunction "D6_D6") (pintype "bidirectional"))
    )
    (net (code "426") (name "unconnected-(U$12-PadD7)") (class "Default")
      (node (ref "U$12") (pin "D7") (pinfunction "D7_D7") (pintype "bidirectional"))
    )
    (net (code "427") (name "unconnected-(U$12-PadD8)") (class "Default")
      (node (ref "U$12") (pin "D8") (pinfunction "D8_D8") (pintype "bidirectional"))
    )
    (net (code "428") (name "unconnected-(U$12-PadD9)") (class "Default")
      (node (ref "U$12") (pin "D9") (pinfunction "D9_D9") (pintype "bidirectional"))
    )
    (net (code "429") (name "unconnected-(U$12-PadD10)") (class "Default")
      (node (ref "U$12") (pin "D10") (pinfunction "D10_D10") (pintype "bidirectional"))
    )
    (net (code "430") (name "unconnected-(U$12-PadDTR)") (class "Default")
      (node (ref "U$12") (pin "DTR") (pinfunction "DTR_DTR") (pintype "bidirectional"))
    )
    (net (code "431") (name "unconnected-(U$12-PadRAW)") (class "Default")
      (node (ref "U$12") (pin "RAW") (pinfunction "RAW_RAW") (pintype "bidirectional"))
    )
    (net (code "432") (name "unconnected-(U$12-PadRST)") (class "Default")
      (node (ref "U$12") (pin "RST") (pinfunction "RST_RST") (pintype "bidirectional"))
    )
    (net (code "433") (name "unconnected-(U$12-PadRST1)") (class "Default")
      (node (ref "U$12") (pin "RST1") (pinfunction "RST1_RST1") (pintype "bidirectional"))
    )
    (net (code "434") (name "unconnected-(U$12-PadRX1-1)") (class "Default")
      (node (ref "U$12") (pin "RX1-1") (pinfunction "RX1-1_RX1-1") (pintype "bidirectional"))
    )
    (net (code "435") (name "unconnected-(U$12-PadTX0-1)") (class "Default")
      (node (ref "U$12") (pin "TX0-1") (pinfunction "TX0-1_TX0-1") (pintype "bidirectional"))
    )
    (net (code "436") (name "unconnected-(U$12-PadVCC1)") (class "Default")
      (node (ref "U$12") (pin "VCC1") (pinfunction "VCC1_VCC1") (pintype "bidirectional"))
    )
  )
)
